# SynthEvaluationBoard.net
KiCad netlist of a schematic drawn in EAGLE
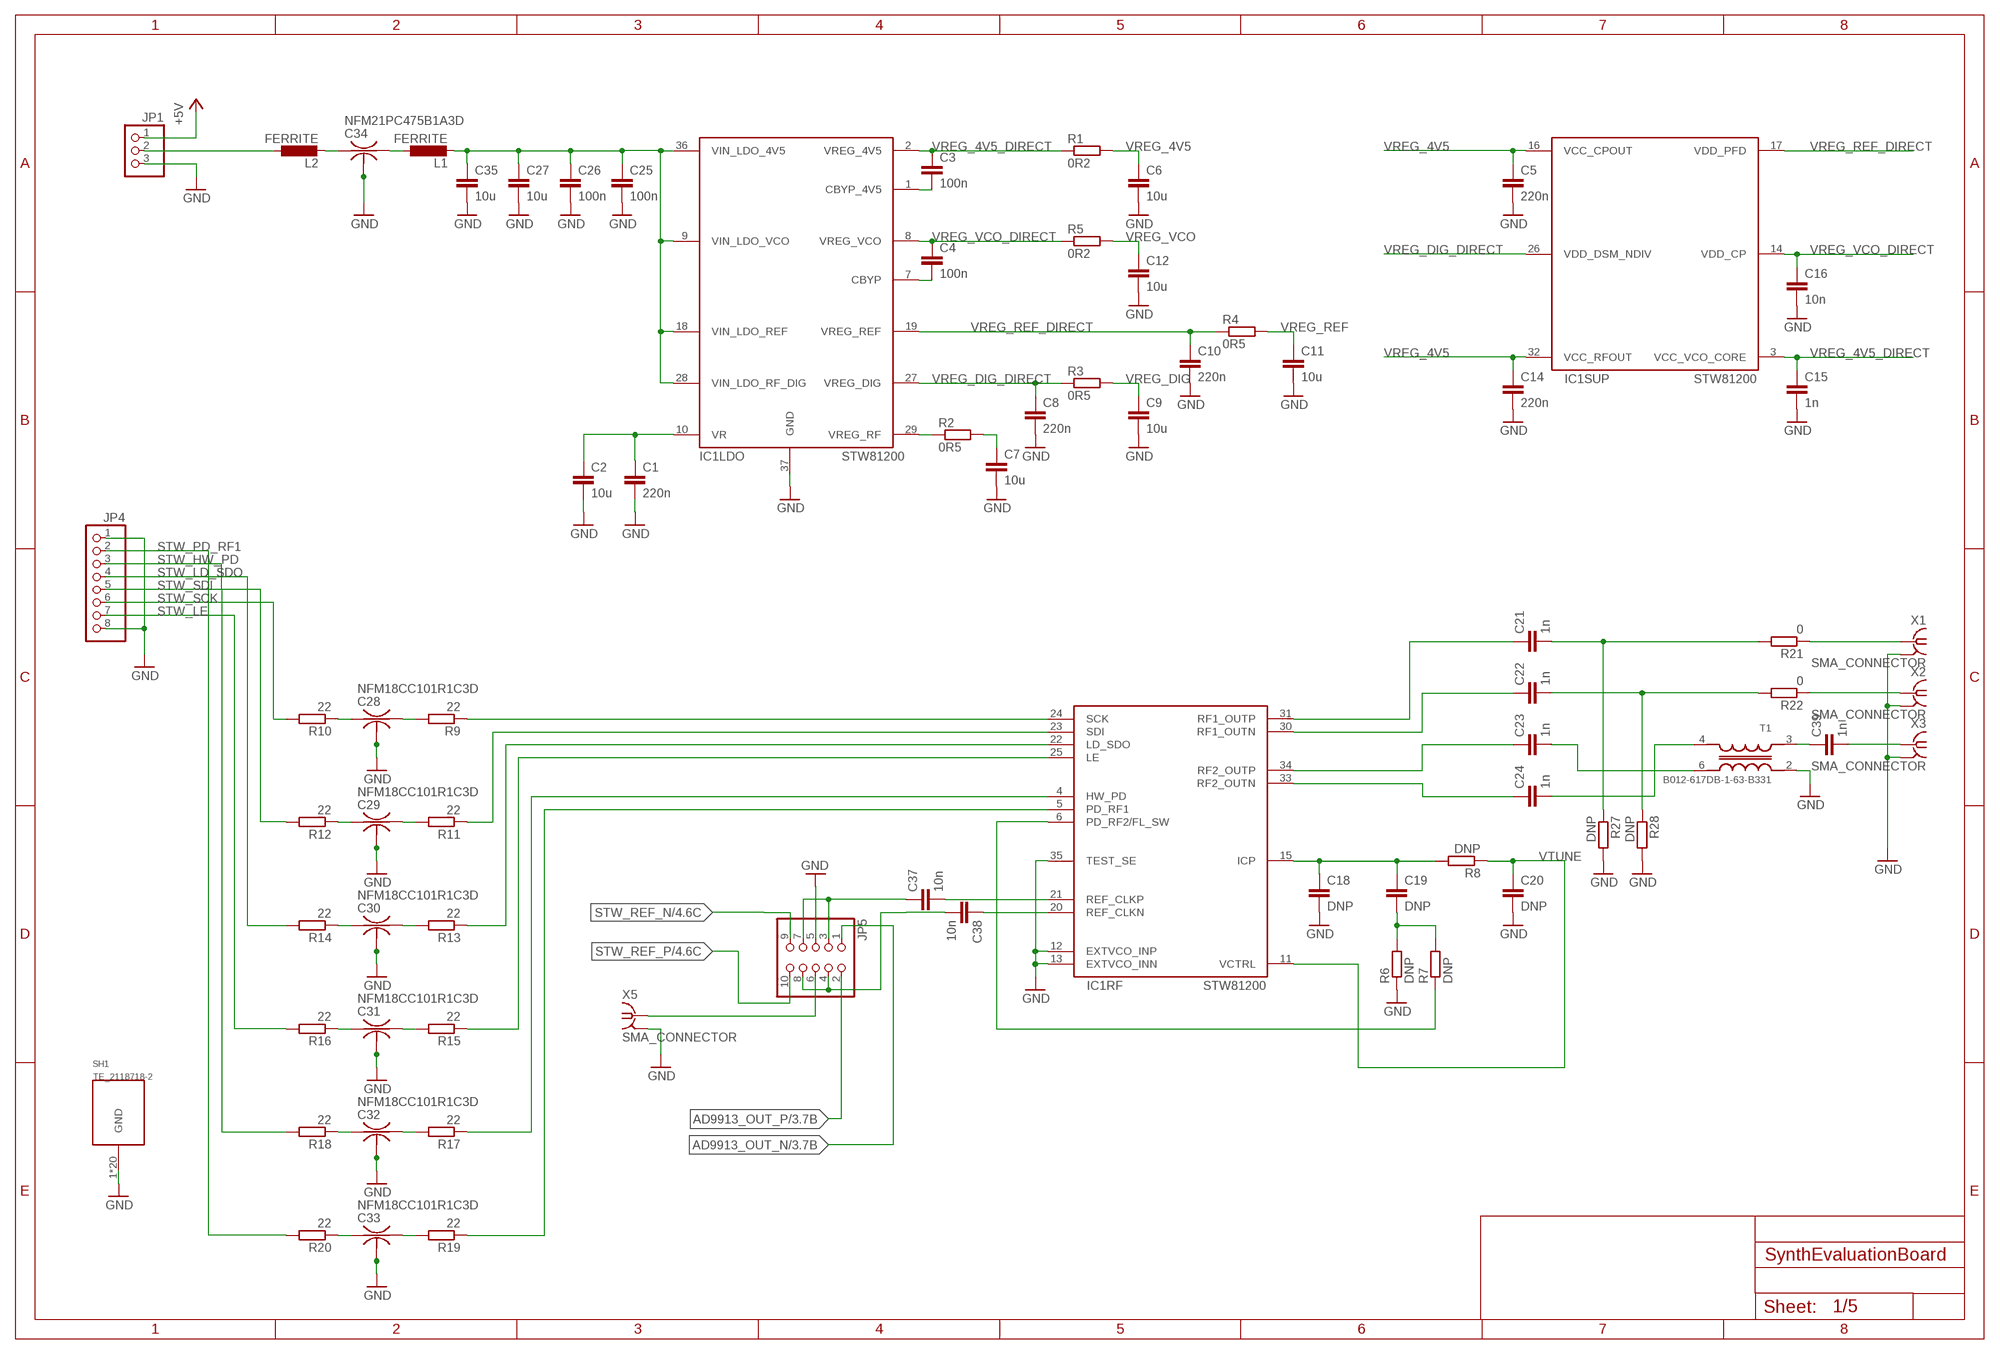
[diagram p0: schematic, sheet 1]
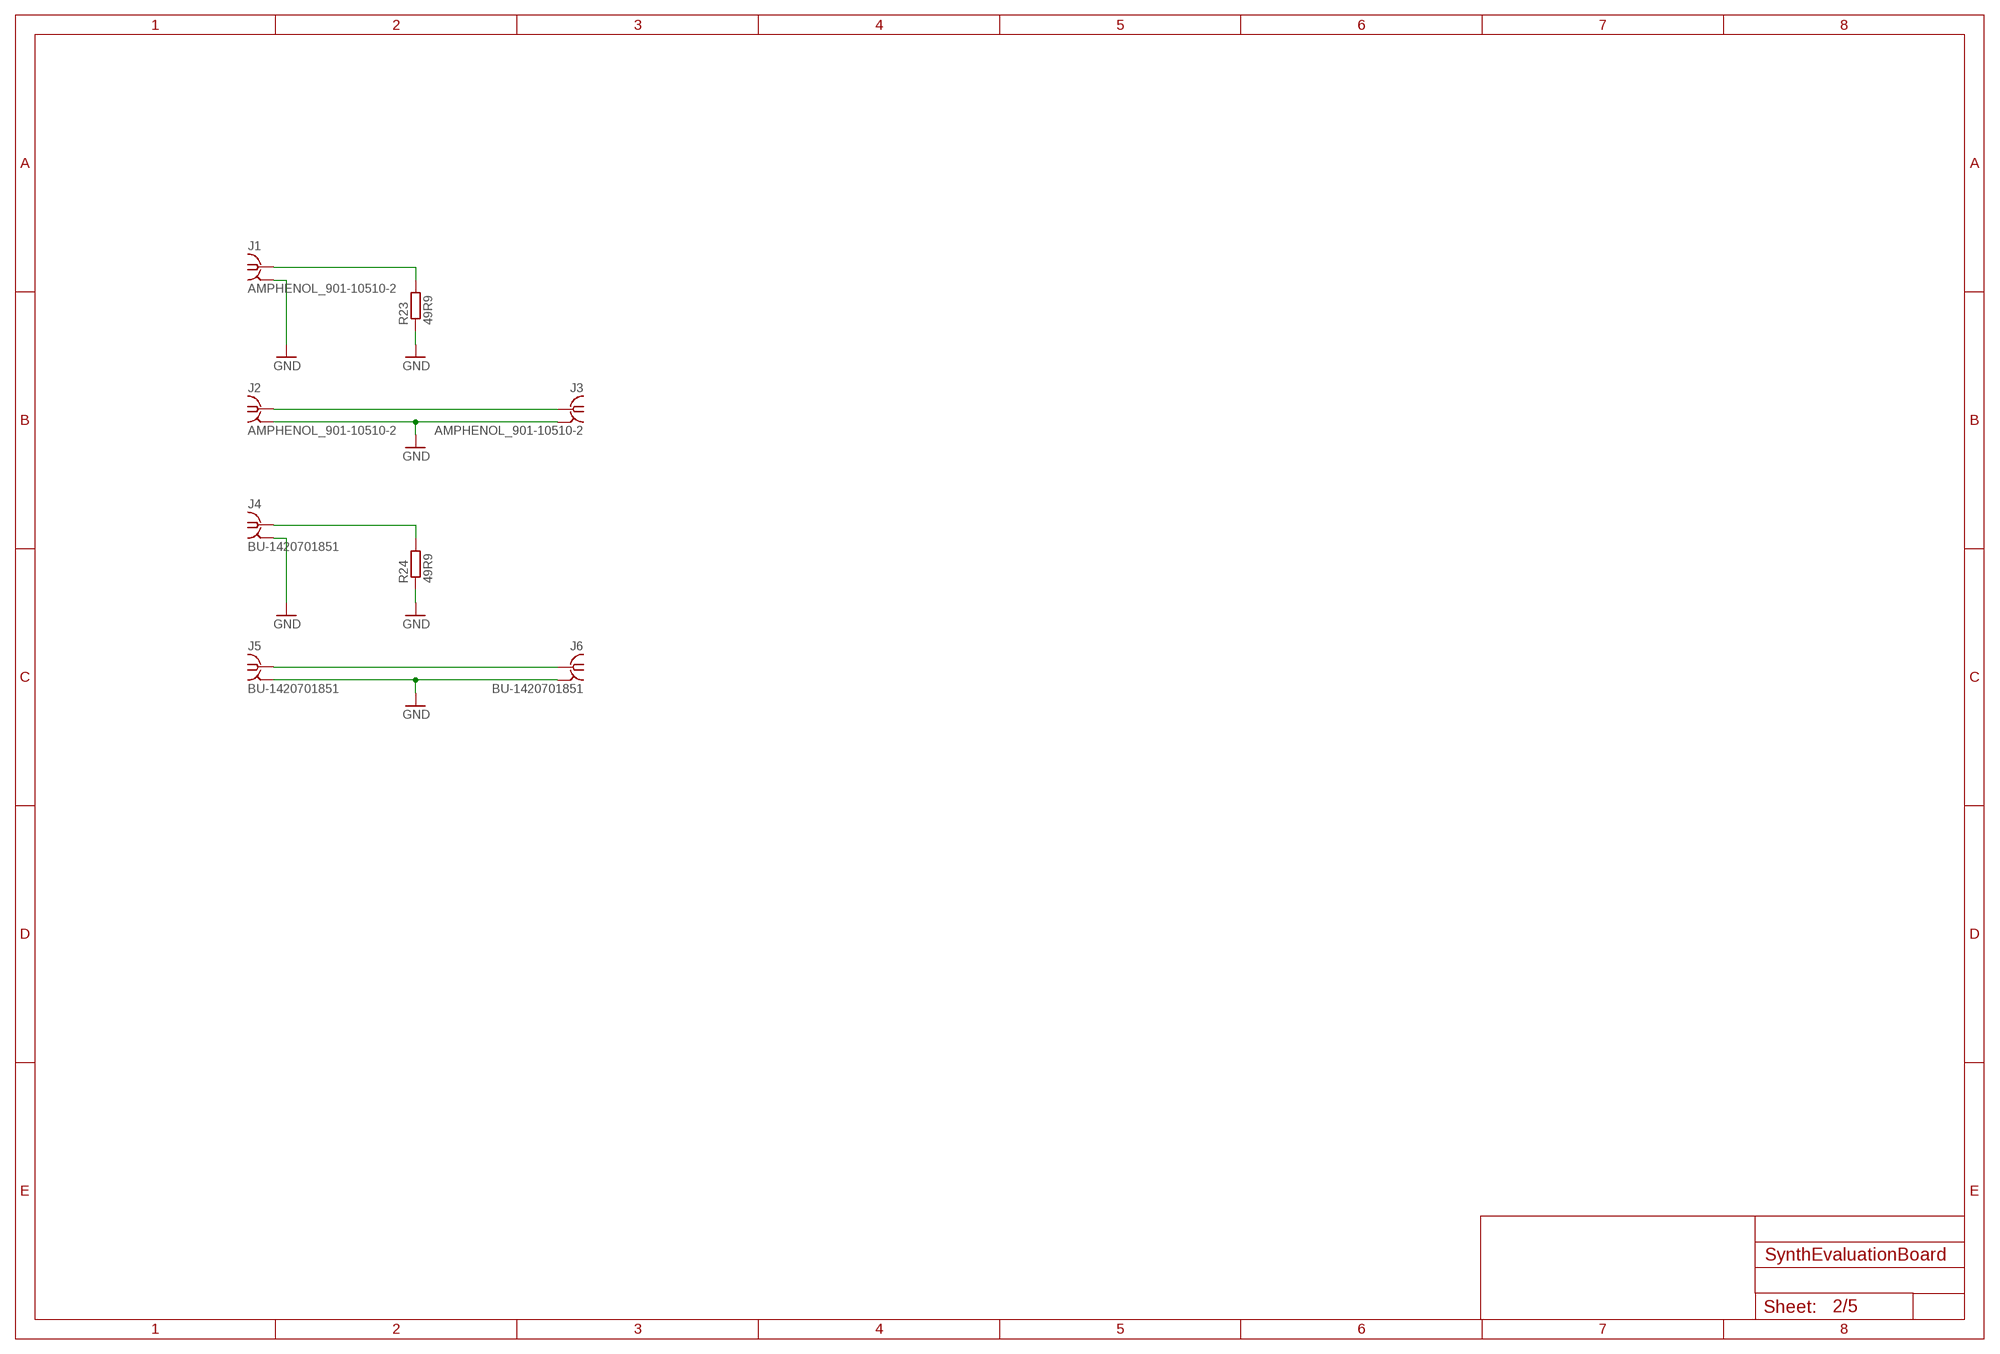
[diagram p1: schematic, sheet 2]
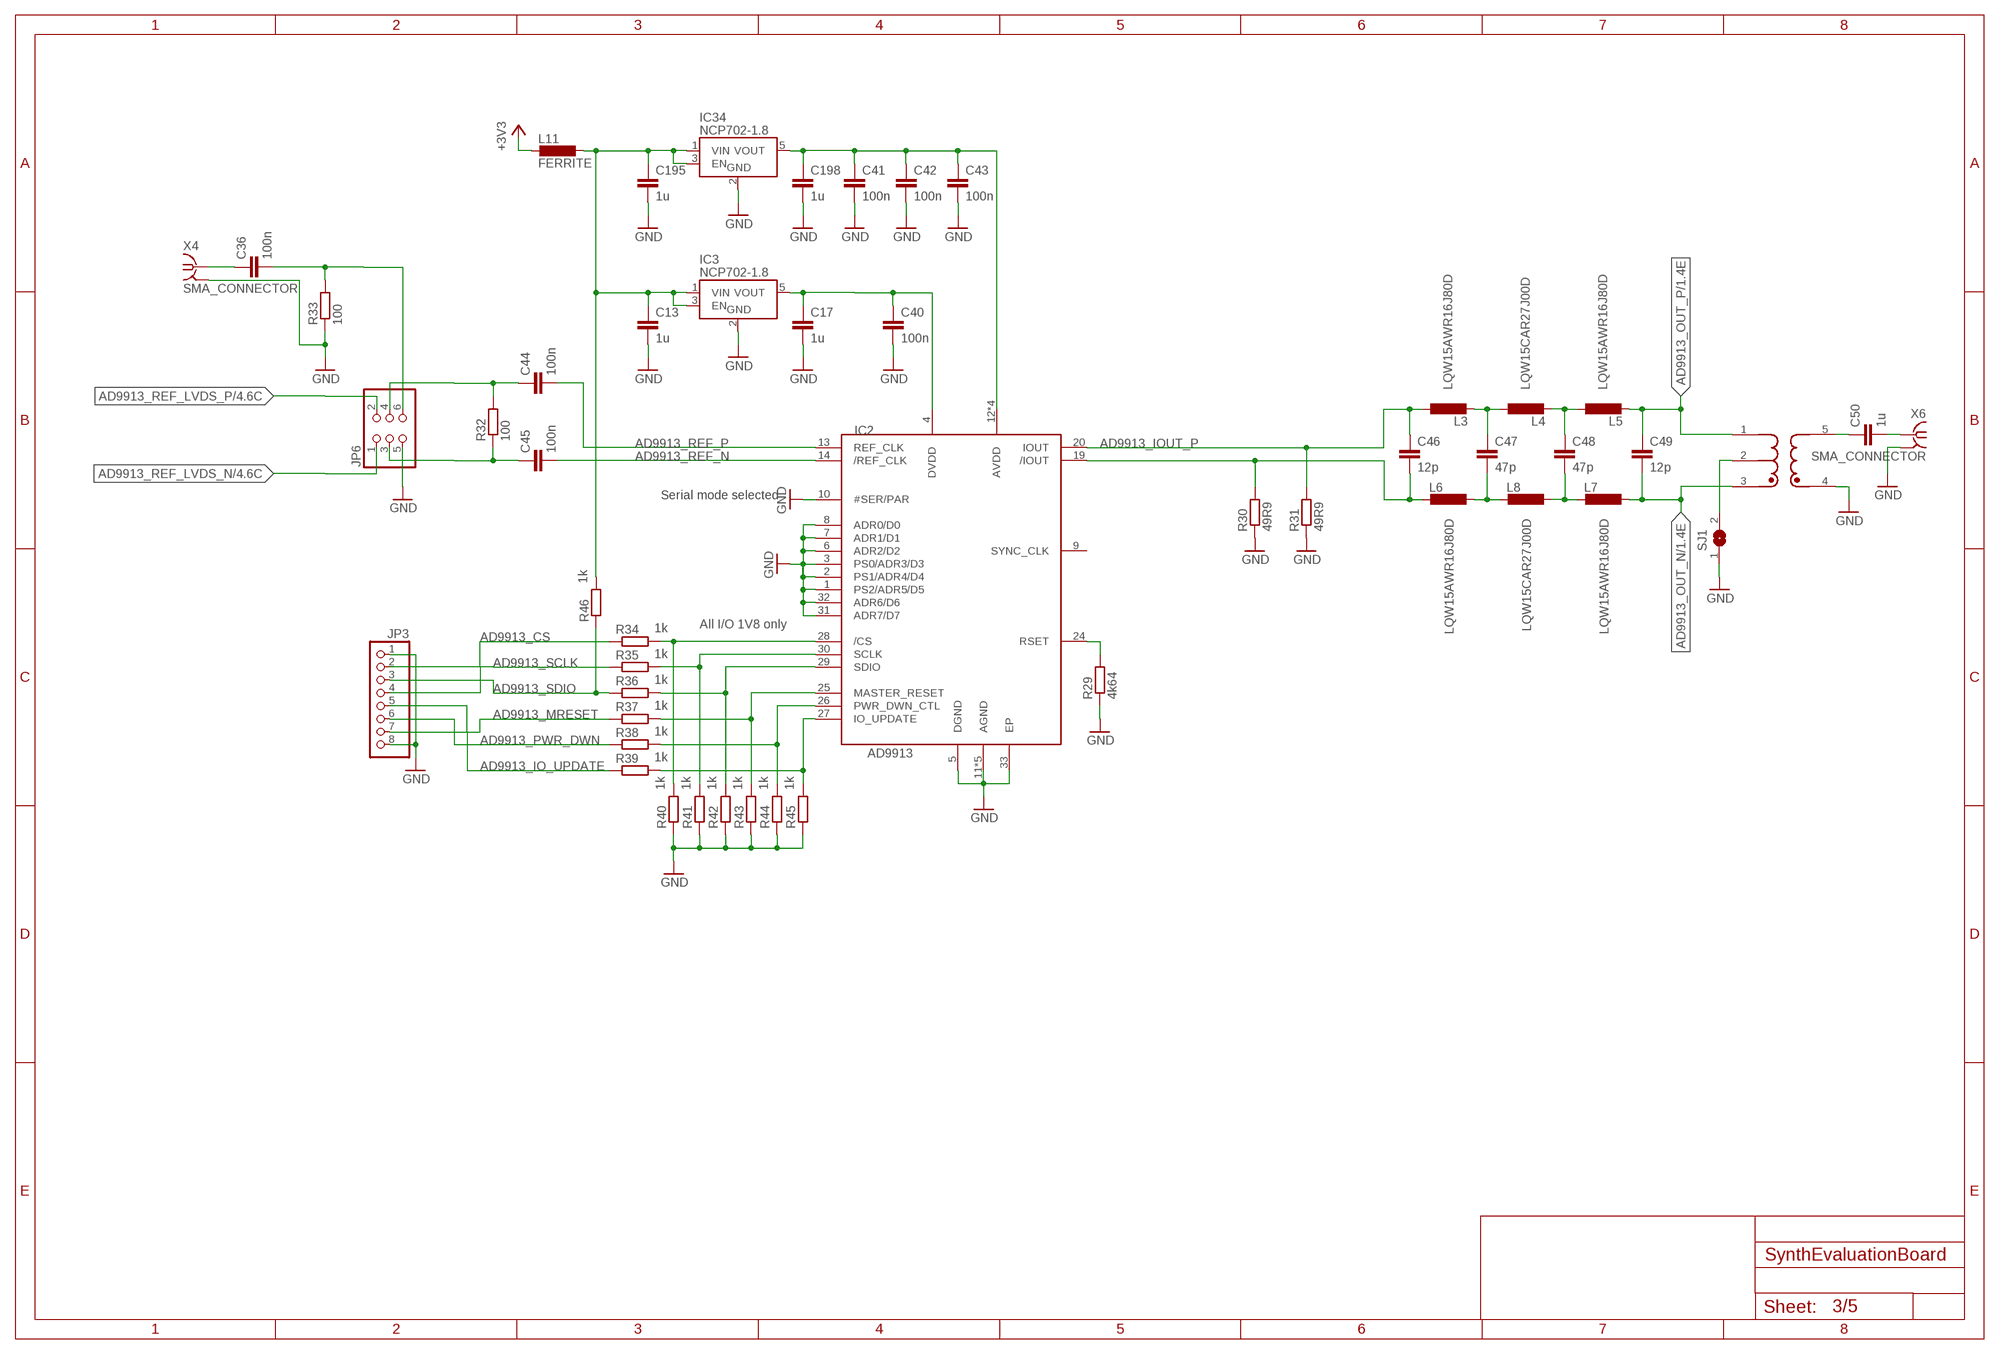
[diagram p2: schematic, sheet 3]
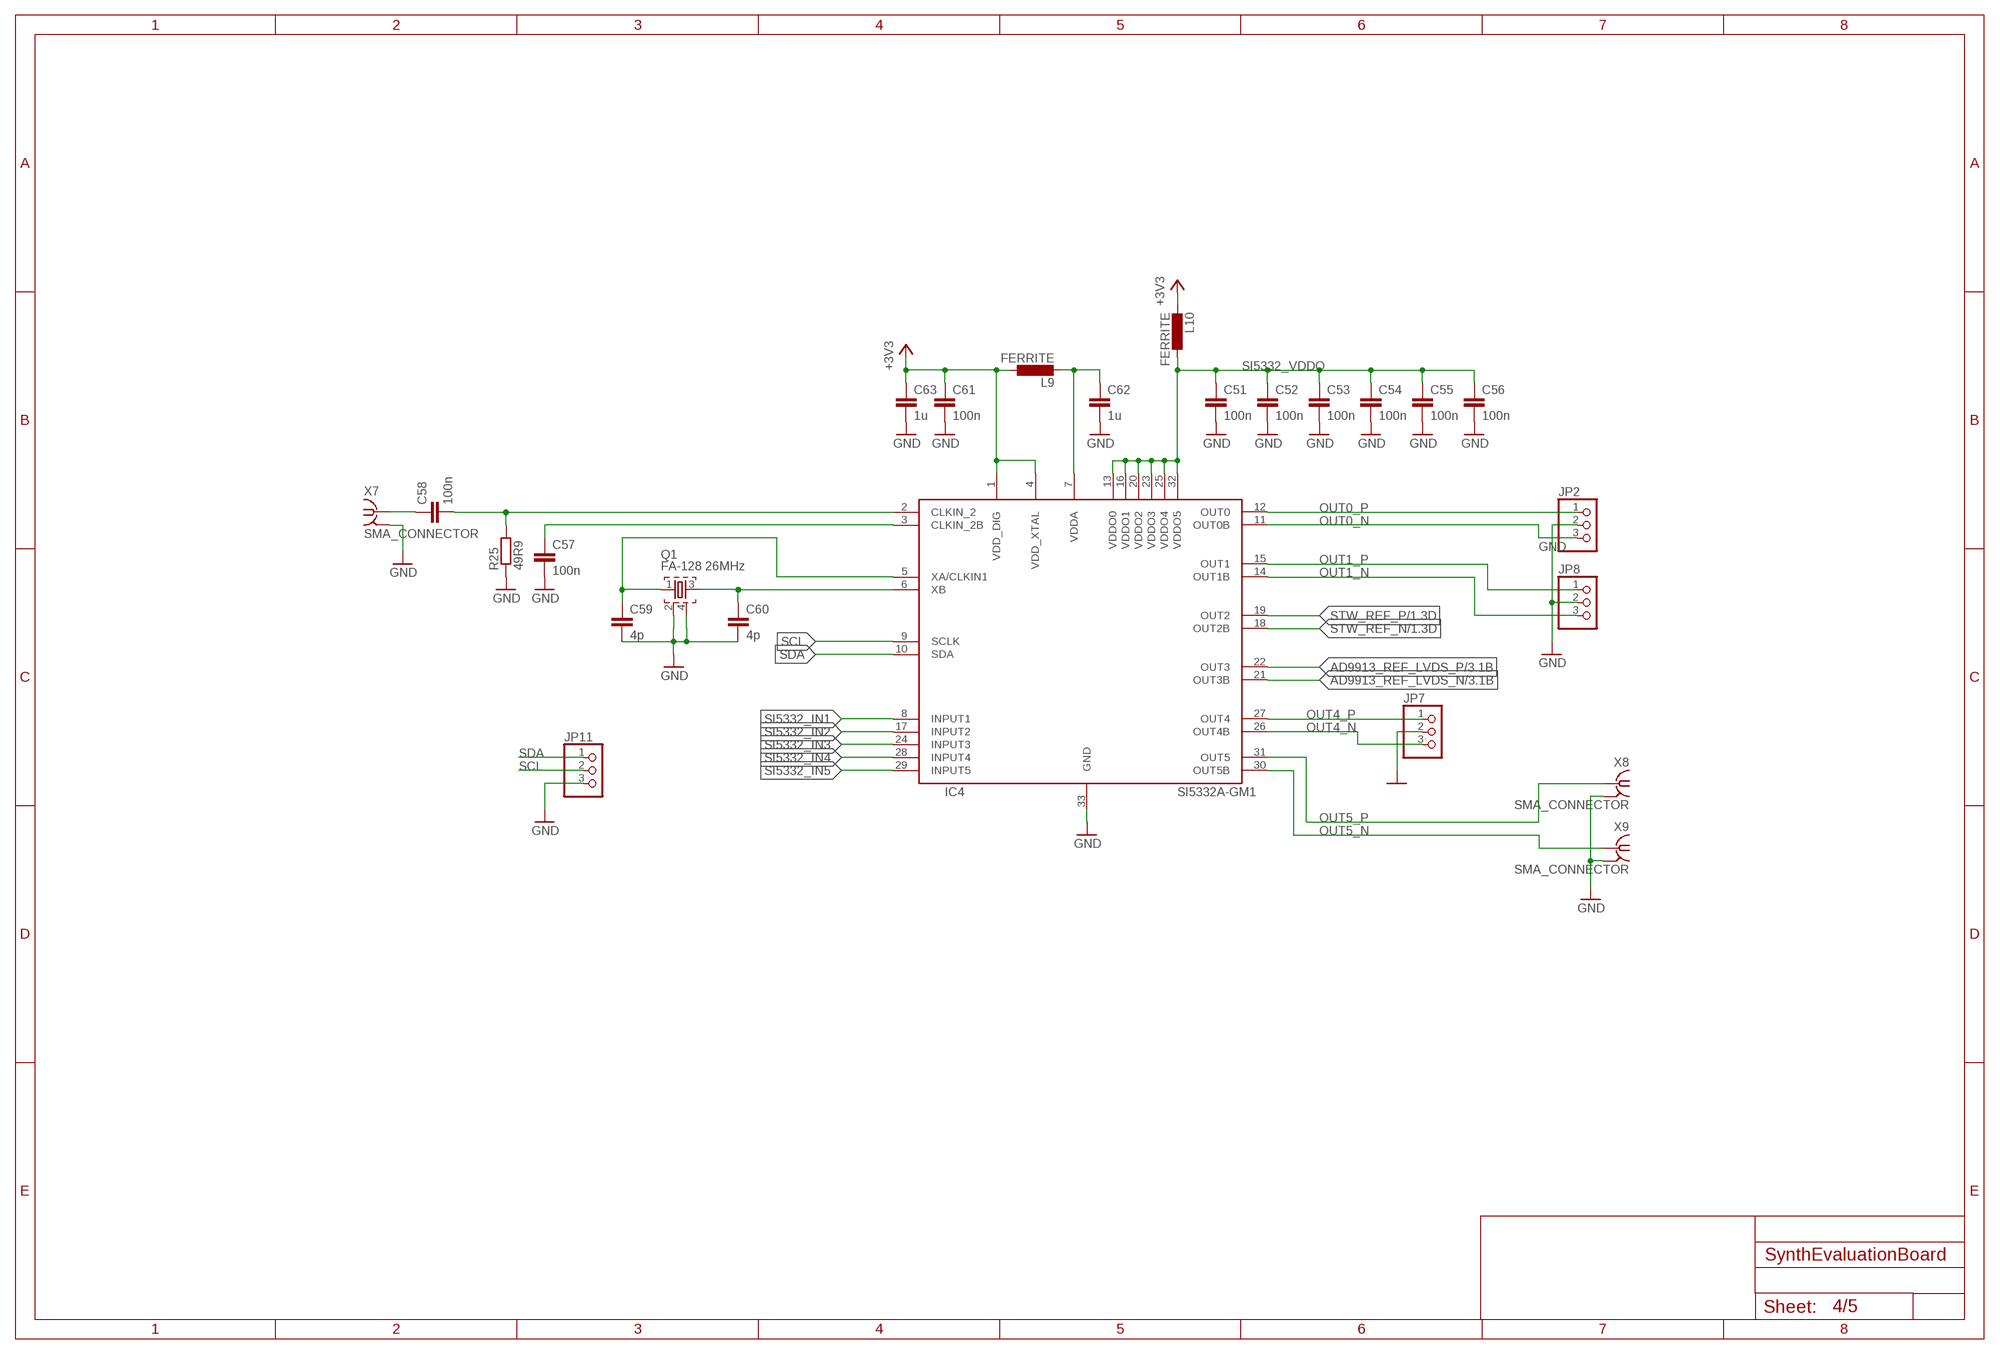
[diagram p3: schematic, sheet 4]
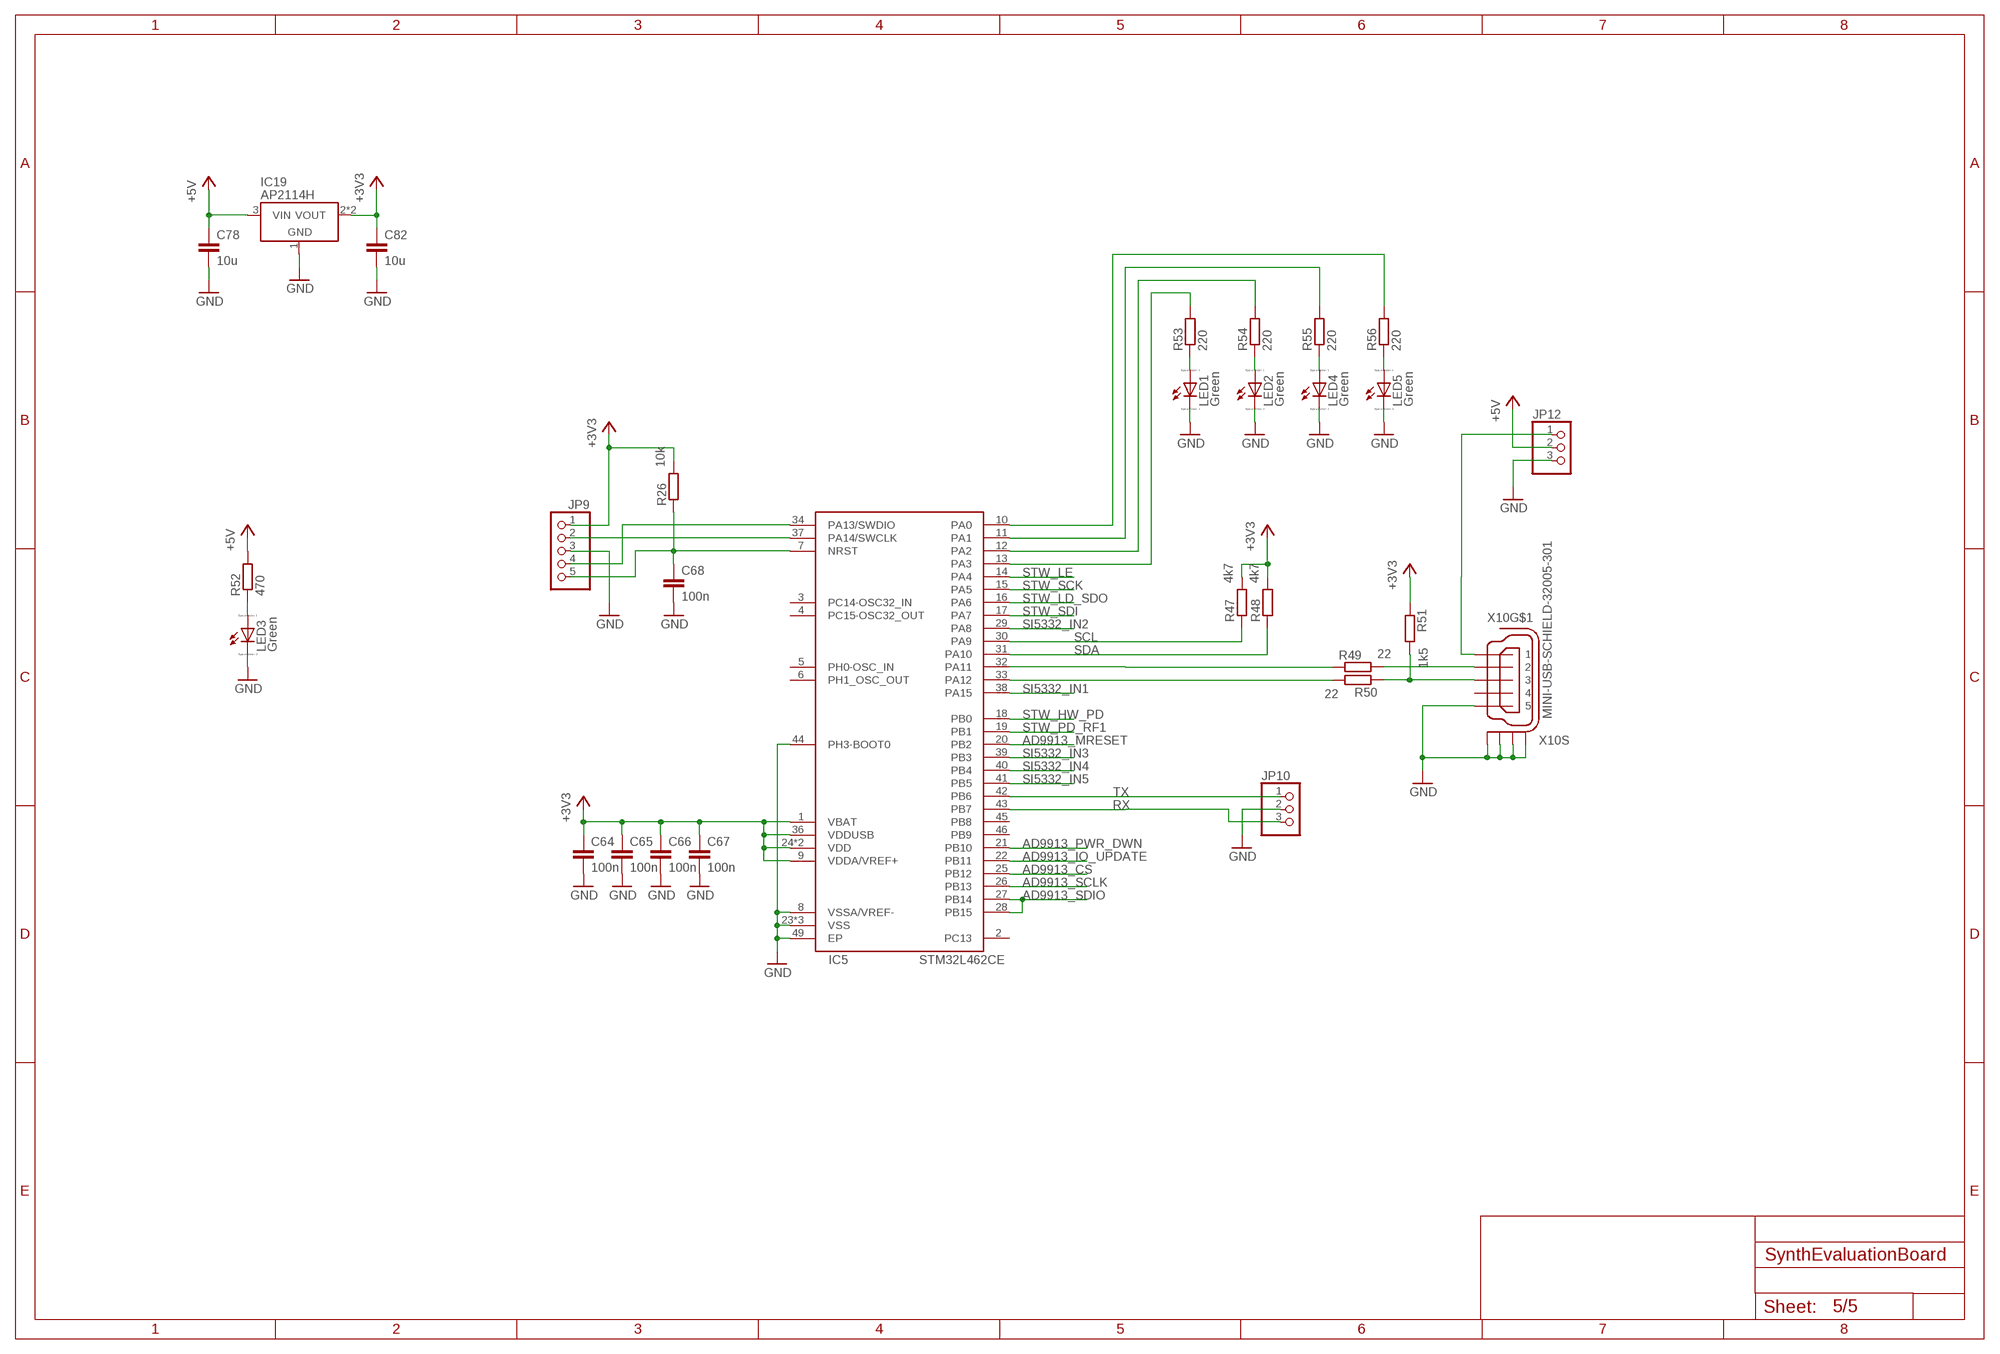
[diagram p4: schematic, sheet 5]

(export (version "E")
  (design (tool "Eeschema 10.0.6"))
  (components
    (comp (ref "C51")
      (value "100n")
      (footprint "eagle-import:C0402")
      (libsource (lib "eagle-import") (part "C-EU?{colon}2C0402"))
    )
    (comp (ref "C52")
      (value "100n")
      (footprint "eagle-import:C0402")
      (libsource (lib "eagle-import") (part "C-EU?{colon}2C0402"))
    )
    (comp (ref "C53")
      (value "100n")
      (footprint "eagle-import:C0402")
      (libsource (lib "eagle-import") (part "C-EU?{colon}2C0402"))
    )
    (comp (ref "C54")
      (value "100n")
      (footprint "eagle-import:C0402")
      (libsource (lib "eagle-import") (part "C-EU?{colon}2C0402"))
    )
    (comp (ref "C55")
      (value "100n")
      (footprint "eagle-import:C0402")
      (libsource (lib "eagle-import") (part "C-EU?{colon}2C0402"))
    )
    (comp (ref "C56")
      (value "100n")
      (footprint "eagle-import:C0402")
      (libsource (lib "eagle-import") (part "C-EU?{colon}2C0402"))
    )
    (comp (ref "C57")
      (value "100n")
      (footprint "eagle-import:C0402")
      (libsource (lib "eagle-import") (part "C-EU?{colon}2C0402"))
    )
    (comp (ref "C58")
      (value "100n")
      (footprint "eagle-import:C0402")
      (libsource (lib "eagle-import") (part "C-EU?{colon}2C0402"))
    )
    (comp (ref "C59")
      (value "4p")
      (footprint "eagle-import:C0402")
      (libsource (lib "eagle-import") (part "C-EU?{colon}2C0402"))
    )
    (comp (ref "C60")
      (value "4p")
      (footprint "eagle-import:C0402")
      (libsource (lib "eagle-import") (part "C-EU?{colon}2C0402"))
    )
    (comp (ref "C61")
      (value "100n")
      (footprint "eagle-import:C0402")
      (libsource (lib "eagle-import") (part "C-EU?{colon}2C0402"))
    )
    (comp (ref "C62")
      (value "1u")
      (footprint "eagle-import:C0402")
      (libsource (lib "eagle-import") (part "C-EU?{colon}2C0402"))
    )
    (comp (ref "C63")
      (value "1u")
      (footprint "eagle-import:C0402")
      (libsource (lib "eagle-import") (part "C-EU?{colon}2C0402"))
    )
    (comp (ref "IC4")
      (value "SI5332A-GM1")
      (footprint "eagle-import:QFN50P500X500X100-33T345N")
      (libsource (lib "eagle-import") (part "SI5332A-GM1"))
    )
    (comp (ref "JP2")
      (value "PINHD-1X3")
      (footprint "eagle-import:1X03")
      (libsource (lib "eagle-import") (part "PINHD-1X3"))
    )
    (comp (ref "JP7")
      (value "PINHD-1X3")
      (footprint "eagle-import:1X03")
      (libsource (lib "eagle-import") (part "PINHD-1X3"))
    )
    (comp (ref "JP8")
      (value "PINHD-1X3")
      (footprint "eagle-import:1X03")
      (libsource (lib "eagle-import") (part "PINHD-1X3"))
    )
    (comp (ref "JP11")
      (value "PINHD-1X3")
      (footprint "eagle-import:1X03")
      (libsource (lib "eagle-import") (part "PINHD-1X3"))
    )
    (comp (ref "L9")
      (value "FERRITE")
      (footprint "eagle-import:R0402")
      (libsource (lib "eagle-import") (part "FERRITE"))
    )
    (comp (ref "L10")
      (value "FERRITE")
      (footprint "eagle-import:R0402")
      (libsource (lib "eagle-import") (part "FERRITE"))
    )
    (comp (ref "Q1")
      (value "FA-128 26MHz")
      (footprint "eagle-import:FA-128")
      (libsource (lib "eagle-import") (part "FA-128"))
    )
    (comp (ref "R25")
      (value "49R9")
      (footprint "eagle-import:R0402")
      (libsource (lib "eagle-import") (part "R-EU_R0402"))
    )
    (comp (ref "X7")
      (value "SMA_CONNECTOR")
      (footprint "eagle-import:J502-ND-142-0711-821_826")
      (libsource (lib "eagle-import") (part "SMA_CONNECTOR"))
    )
    (comp (ref "X8")
      (value "SMA_CONNECTOR")
      (footprint "eagle-import:J502-ND-142-0711-821_826")
      (libsource (lib "eagle-import") (part "SMA_CONNECTOR"))
    )
    (comp (ref "X9")
      (value "SMA_CONNECTOR")
      (footprint "eagle-import:J502-ND-142-0711-821_826")
      (libsource (lib "eagle-import") (part "SMA_CONNECTOR"))
    )
    (comp (ref "B1")
      (value "ETC1-1T-2")
      (footprint "eagle-import:SM-22")
      (libsource (lib "eagle-import") (part "ETC1-1T"))
    )
    (comp (ref "C13")
      (value "1u")
      (footprint "eagle-import:C0402")
      (libsource (lib "eagle-import") (part "C-EU?{colon}2C0402"))
    )
    (comp (ref "C17")
      (value "1u")
      (footprint "eagle-import:C0402")
      (libsource (lib "eagle-import") (part "C-EU?{colon}2C0402"))
    )
    (comp (ref "C36")
      (value "100n")
      (footprint "eagle-import:C0402")
      (libsource (lib "eagle-import") (part "C-EU?{colon}2C0402"))
    )
    (comp (ref "C40")
      (value "100n")
      (footprint "eagle-import:C0402")
      (libsource (lib "eagle-import") (part "C-EU?{colon}2C0402"))
    )
    (comp (ref "C41")
      (value "100n")
      (footprint "eagle-import:C0402")
      (libsource (lib "eagle-import") (part "C-EU?{colon}2C0402"))
    )
    (comp (ref "C42")
      (value "100n")
      (footprint "eagle-import:C0402")
      (libsource (lib "eagle-import") (part "C-EU?{colon}2C0402"))
    )
    (comp (ref "C43")
      (value "100n")
      (footprint "eagle-import:C0402")
      (libsource (lib "eagle-import") (part "C-EU?{colon}2C0402"))
    )
    (comp (ref "C44")
      (value "100n")
      (footprint "eagle-import:C0402")
      (libsource (lib "eagle-import") (part "C-EU?{colon}2C0402"))
    )
    (comp (ref "C45")
      (value "100n")
      (footprint "eagle-import:C0402")
      (libsource (lib "eagle-import") (part "C-EU?{colon}2C0402"))
    )
    (comp (ref "C46")
      (value "12p")
      (footprint "eagle-import:C0402")
      (libsource (lib "eagle-import") (part "C-EU?{colon}2C0402"))
    )
    (comp (ref "C47")
      (value "47p")
      (footprint "eagle-import:C0402")
      (libsource (lib "eagle-import") (part "C-EU?{colon}2C0402"))
    )
    (comp (ref "C48")
      (value "47p")
      (footprint "eagle-import:C0402")
      (libsource (lib "eagle-import") (part "C-EU?{colon}2C0402"))
    )
    (comp (ref "C49")
      (value "12p")
      (footprint "eagle-import:C0402")
      (libsource (lib "eagle-import") (part "C-EU?{colon}2C0402"))
    )
    (comp (ref "C50")
      (value "1u")
      (footprint "eagle-import:C0402")
      (libsource (lib "eagle-import") (part "C-EU?{colon}2C0402"))
    )
    (comp (ref "C195")
      (value "1u")
      (footprint "eagle-import:C0402")
      (libsource (lib "eagle-import") (part "C-EU?{colon}2C0402"))
    )
    (comp (ref "C198")
      (value "1u")
      (footprint "eagle-import:C0402")
      (libsource (lib "eagle-import") (part "C-EU?{colon}2C0402"))
    )
    (comp (ref "IC2")
      (value "AD9913")
      (footprint "eagle-import:QFN50P500X500X80-33T310")
      (libsource (lib "eagle-import") (part "AD9913"))
    )
    (comp (ref "IC3")
      (value "NCP702-1.8")
      (footprint "eagle-import:SOT95P240X110-5")
      (libsource (lib "eagle-import") (part "NCP702"))
    )
    (comp (ref "IC34")
      (value "NCP702-1.8")
      (footprint "eagle-import:SOT95P240X110-5")
      (libsource (lib "eagle-import") (part "NCP702"))
    )
    (comp (ref "JP3")
      (value "PINHD-1X8")
      (footprint "eagle-import:1X08")
      (libsource (lib "eagle-import") (part "PINHD-1X8"))
    )
    (comp (ref "JP6")
      (value "PINHD-2X3")
      (footprint "eagle-import:2X03")
      (libsource (lib "eagle-import") (part "PINHD-2X3"))
    )
    (comp (ref "L3")
      (value "LQW15AWR16J80D")
      (footprint "eagle-import:L0402")
      (libsource (lib "eagle-import") (part "INDUCTOR0402"))
    )
    (comp (ref "L4")
      (value "LQW15CAR27J00D")
      (footprint "eagle-import:L0402")
      (libsource (lib "eagle-import") (part "INDUCTOR0402"))
    )
    (comp (ref "L5")
      (value "LQW15AWR16J80D")
      (footprint "eagle-import:L0402")
      (libsource (lib "eagle-import") (part "INDUCTOR0402"))
    )
    (comp (ref "L6")
      (value "LQW15AWR16J80D")
      (footprint "eagle-import:L0402")
      (libsource (lib "eagle-import") (part "INDUCTOR0402"))
    )
    (comp (ref "L7")
      (value "LQW15AWR16J80D")
      (footprint "eagle-import:L0402")
      (libsource (lib "eagle-import") (part "INDUCTOR0402"))
    )
    (comp (ref "L8")
      (value "LQW15CAR27J00D")
      (footprint "eagle-import:L0402")
      (libsource (lib "eagle-import") (part "INDUCTOR0402"))
    )
    (comp (ref "L11")
      (value "FERRITE")
      (footprint "eagle-import:R0402")
      (libsource (lib "eagle-import") (part "FERRITE"))
    )
    (comp (ref "R29")
      (value "4k64")
      (footprint "eagle-import:R0402")
      (libsource (lib "eagle-import") (part "R-EU_R0402"))
    )
    (comp (ref "R30")
      (value "49R9")
      (footprint "eagle-import:R0402")
      (libsource (lib "eagle-import") (part "R-EU_R0402"))
    )
    (comp (ref "R31")
      (value "49R9")
      (footprint "eagle-import:R0402")
      (libsource (lib "eagle-import") (part "R-EU_R0402"))
    )
    (comp (ref "R32")
      (value "100")
      (footprint "eagle-import:R0402")
      (libsource (lib "eagle-import") (part "R-EU_R0402"))
    )
    (comp (ref "R33")
      (value "100")
      (footprint "eagle-import:R0402")
      (libsource (lib "eagle-import") (part "R-EU_R0402"))
    )
    (comp (ref "R34")
      (value "1k")
      (footprint "eagle-import:R0402")
      (libsource (lib "eagle-import") (part "R-EU_R0402"))
    )
    (comp (ref "R35")
      (value "1k")
      (footprint "eagle-import:R0402")
      (libsource (lib "eagle-import") (part "R-EU_R0402"))
    )
    (comp (ref "R36")
      (value "1k")
      (footprint "eagle-import:R0402")
      (libsource (lib "eagle-import") (part "R-EU_R0402"))
    )
    (comp (ref "R37")
      (value "1k")
      (footprint "eagle-import:R0402")
      (libsource (lib "eagle-import") (part "R-EU_R0402"))
    )
    (comp (ref "R38")
      (value "1k")
      (footprint "eagle-import:R0402")
      (libsource (lib "eagle-import") (part "R-EU_R0402"))
    )
    (comp (ref "R39")
      (value "1k")
      (footprint "eagle-import:R0402")
      (libsource (lib "eagle-import") (part "R-EU_R0402"))
    )
    (comp (ref "R40")
      (value "1k")
      (footprint "eagle-import:R0402")
      (libsource (lib "eagle-import") (part "R-EU_R0402"))
    )
    (comp (ref "R41")
      (value "1k")
      (footprint "eagle-import:R0402")
      (libsource (lib "eagle-import") (part "R-EU_R0402"))
    )
    (comp (ref "R42")
      (value "1k")
      (footprint "eagle-import:R0402")
      (libsource (lib "eagle-import") (part "R-EU_R0402"))
    )
    (comp (ref "R43")
      (value "1k")
      (footprint "eagle-import:R0402")
      (libsource (lib "eagle-import") (part "R-EU_R0402"))
    )
    (comp (ref "R44")
      (value "1k")
      (footprint "eagle-import:R0402")
      (libsource (lib "eagle-import") (part "R-EU_R0402"))
    )
    (comp (ref "R45")
      (value "1k")
      (footprint "eagle-import:R0402")
      (libsource (lib "eagle-import") (part "R-EU_R0402"))
    )
    (comp (ref "R46")
      (value "1k")
      (footprint "eagle-import:R0402")
      (libsource (lib "eagle-import") (part "R-EU_R0402"))
    )
    (comp (ref "SJ1") (value "SJ") (footprint "eagle-import:SJ") (libsource (lib "eagle-import") (part "SJ")))
    (comp (ref "X4")
      (value "SMA_CONNECTOR")
      (footprint "eagle-import:J502-ND-142-0711-821_826")
      (libsource (lib "eagle-import") (part "SMA_CONNECTOR"))
    )
    (comp (ref "X6")
      (value "SMA_CONNECTOR")
      (footprint "eagle-import:J502-ND-142-0711-821_826")
      (libsource (lib "eagle-import") (part "SMA_CONNECTOR"))
    )
    (comp (ref "J1")
      (value "AMPHENOL_901-10510-2")
      (footprint "eagle-import:AMPHENOL_901-10510-2")
      (libsource (lib "eagle-import") (part "AMPHENOL_901-10510-2"))
    )
    (comp (ref "J2")
      (value "AMPHENOL_901-10510-2")
      (footprint "eagle-import:AMPHENOL_901-10510-2")
      (libsource (lib "eagle-import") (part "AMPHENOL_901-10510-2"))
    )
    (comp (ref "J3")
      (value "AMPHENOL_901-10510-2")
      (footprint "eagle-import:AMPHENOL_901-10510-2")
      (libsource (lib "eagle-import") (part "AMPHENOL_901-10510-2"))
    )
    (comp (ref "J4")
      (value "BU-1420701851")
      (footprint "eagle-import:BU-1420701851")
      (libsource (lib "eagle-import") (part "BU-1420701851"))
    )
    (comp (ref "J5")
      (value "BU-1420701851")
      (footprint "eagle-import:BU-1420701851")
      (libsource (lib "eagle-import") (part "BU-1420701851"))
    )
    (comp (ref "J6")
      (value "BU-1420701851")
      (footprint "eagle-import:BU-1420701851")
      (libsource (lib "eagle-import") (part "BU-1420701851"))
    )
    (comp (ref "R23")
      (value "49R9")
      (footprint "eagle-import:R0402")
      (libsource (lib "eagle-import") (part "R-EU_R0402"))
    )
    (comp (ref "R24")
      (value "49R9")
      (footprint "eagle-import:R0402")
      (libsource (lib "eagle-import") (part "R-EU_R0402"))
    )
    (comp (ref "C64")
      (value "100n")
      (footprint "eagle-import:C0402")
      (libsource (lib "eagle-import") (part "C-EU?{colon}2C0402"))
    )
    (comp (ref "C65")
      (value "100n")
      (footprint "eagle-import:C0402")
      (libsource (lib "eagle-import") (part "C-EU?{colon}2C0402"))
    )
    (comp (ref "C66")
      (value "100n")
      (footprint "eagle-import:C0402")
      (libsource (lib "eagle-import") (part "C-EU?{colon}2C0402"))
    )
    (comp (ref "C67")
      (value "100n")
      (footprint "eagle-import:C0402")
      (libsource (lib "eagle-import") (part "C-EU?{colon}2C0402"))
    )
    (comp (ref "C68")
      (value "100n")
      (footprint "eagle-import:C0402")
      (libsource (lib "eagle-import") (part "C-EU?{colon}2C0402"))
    )
    (comp (ref "C78")
      (value "10u")
      (footprint "eagle-import:C1206")
      (libsource (lib "eagle-import") (part "C-EUC1206"))
    )
    (comp (ref "C82")
      (value "10u")
      (footprint "eagle-import:C1206")
      (libsource (lib "eagle-import") (part "C-EUC1206"))
    )
    (comp (ref "IC5")
      (value "STM32L462CE")
      (footprint "eagle-import:QFN50P700X700X60-49T560N")
      (libsource (lib "eagle-import") (part "STM32L462CE"))
    )
    (comp (ref "IC19")
      (value "AP2114H")
      (footprint "eagle-import:SOT230P700X180-4")
      (libsource (lib "eagle-import") (part "AP2114H"))
    )
    (comp (ref "JP9")
      (value "PINHD-1X5")
      (footprint "eagle-import:1X05")
      (libsource (lib "eagle-import") (part "PINHD-1X5"))
    )
    (comp (ref "JP10")
      (value "PINHD-1X3")
      (footprint "eagle-import:1X03")
      (libsource (lib "eagle-import") (part "PINHD-1X3"))
    )
    (comp (ref "JP12")
      (value "PINHD-1X3")
      (footprint "eagle-import:1X03")
      (libsource (lib "eagle-import") (part "PINHD-1X3"))
    )
    (comp (ref "LED1")
      (value "Green")
      (footprint "eagle-import:LED_SML0603")
      (libsource (lib "eagle-import") (part "LED_ESML0603"))
    )
    (comp (ref "LED2")
      (value "Green")
      (footprint "eagle-import:LED_SML0603")
      (libsource (lib "eagle-import") (part "LED_ESML0603"))
    )
    (comp (ref "LED3")
      (value "Green")
      (footprint "eagle-import:LED_SML0603")
      (libsource (lib "eagle-import") (part "LED_ESML0603"))
    )
    (comp (ref "LED4")
      (value "Green")
      (footprint "eagle-import:LED_SML0603")
      (libsource (lib "eagle-import") (part "LED_ESML0603"))
    )
    (comp (ref "LED5")
      (value "Green")
      (footprint "eagle-import:LED_SML0603")
      (libsource (lib "eagle-import") (part "LED_ESML0603"))
    )
    (comp (ref "R26")
      (value "10k")
      (footprint "eagle-import:R0402")
      (libsource (lib "eagle-import") (part "R-EU_R0402"))
    )
    (comp (ref "R47")
      (value "4k7")
      (footprint "eagle-import:R0402")
      (libsource (lib "eagle-import") (part "R-EU_R0402"))
    )
    (comp (ref "R48")
      (value "4k7")
      (footprint "eagle-import:R0402")
      (libsource (lib "eagle-import") (part "R-EU_R0402"))
    )
    (comp (ref "R49")
      (value "22")
      (footprint "eagle-import:R0402")
      (libsource (lib "eagle-import") (part "R-EU_R0402"))
    )
    (comp (ref "R50")
      (value "22")
      (footprint "eagle-import:R0402")
      (libsource (lib "eagle-import") (part "R-EU_R0402"))
    )
    (comp (ref "R51")
      (value "1k5")
      (footprint "eagle-import:R0402")
      (libsource (lib "eagle-import") (part "R-EU_R0402"))
    )
    (comp (ref "R52")
      (value "470")
      (footprint "eagle-import:R0402")
      (libsource (lib "eagle-import") (part "R-EU_R0402"))
    )
    (comp (ref "R53")
      (value "220")
      (footprint "eagle-import:R0402")
      (libsource (lib "eagle-import") (part "R-EU_R0402"))
    )
    (comp (ref "R54")
      (value "220")
      (footprint "eagle-import:R0402")
      (libsource (lib "eagle-import") (part "R-EU_R0402"))
    )
    (comp (ref "R55")
      (value "220")
      (footprint "eagle-import:R0402")
      (libsource (lib "eagle-import") (part "R-EU_R0402"))
    )
    (comp (ref "R56")
      (value "220")
      (footprint "eagle-import:R0402")
      (libsource (lib "eagle-import") (part "R-EU_R0402"))
    )
    (comp (ref "X10")
      (value "MINI-USB-SCHIELD-32005-301")
      (footprint "eagle-import:32005-301")
      (libsource (lib "eagle-import") (part "MINI-USB-SCHIELD-32005-301"))
    )
    (comp (ref "C1")
      (value "220n")
      (footprint "eagle-import:C0402")
      (libsource (lib "eagle-import") (part "C-EUC0402"))
    )
    (comp (ref "C2")
      (value "10u")
      (footprint "eagle-import:C0603")
      (libsource (lib "eagle-import") (part "rcl_334_C-EUC0603"))
    )
    (comp (ref "C3")
      (value "100n")
      (footprint "eagle-import:C0402")
      (libsource (lib "eagle-import") (part "C-EUC0402"))
    )
    (comp (ref "C4")
      (value "100n")
      (footprint "eagle-import:C0402")
      (libsource (lib "eagle-import") (part "C-EUC0402"))
    )
    (comp (ref "C5")
      (value "220n")
      (footprint "eagle-import:C0402")
      (libsource (lib "eagle-import") (part "C-EUC0402"))
    )
    (comp (ref "C6")
      (value "10u")
      (footprint "eagle-import:C0603")
      (libsource (lib "eagle-import") (part "rcl_334_C-EUC0603"))
    )
    (comp (ref "C7")
      (value "10u")
      (footprint "eagle-import:C0603")
      (libsource (lib "eagle-import") (part "rcl_334_C-EUC0603"))
    )
    (comp (ref "C8")
      (value "220n")
      (footprint "eagle-import:C0402")
      (libsource (lib "eagle-import") (part "C-EUC0402"))
    )
    (comp (ref "C9")
      (value "10u")
      (footprint "eagle-import:C0603")
      (libsource (lib "eagle-import") (part "rcl_334_C-EUC0603"))
    )
    (comp (ref "C10")
      (value "220n")
      (footprint "eagle-import:C0402")
      (libsource (lib "eagle-import") (part "C-EUC0402"))
    )
    (comp (ref "C11")
      (value "10u")
      (footprint "eagle-import:C0603")
      (libsource (lib "eagle-import") (part "rcl_334_C-EUC0603"))
    )
    (comp (ref "C12")
      (value "10u")
      (footprint "eagle-import:C0603")
      (libsource (lib "eagle-import") (part "rcl_334_C-EUC0603"))
    )
    (comp (ref "C14")
      (value "220n")
      (footprint "eagle-import:C0402")
      (libsource (lib "eagle-import") (part "C-EUC0402"))
    )
    (comp (ref "C15")
      (value "1n")
      (footprint "eagle-import:C0402")
      (libsource (lib "eagle-import") (part "C-EUC0402"))
    )
    (comp (ref "C16")
      (value "10n")
      (footprint "eagle-import:C0402")
      (libsource (lib "eagle-import") (part "C-EUC0402"))
    )
    (comp (ref "C18")
      (value "DNP")
      (footprint "eagle-import:C0402")
      (libsource (lib "eagle-import") (part "C-EUC0402"))
    )
    (comp (ref "C19")
      (value "DNP")
      (footprint "eagle-import:C0402")
      (libsource (lib "eagle-import") (part "C-EUC0402"))
    )
    (comp (ref "C20")
      (value "DNP")
      (footprint "eagle-import:C0402")
      (libsource (lib "eagle-import") (part "C-EUC0402"))
    )
    (comp (ref "C21")
      (value "1n")
      (footprint "eagle-import:C0402")
      (libsource (lib "eagle-import") (part "C-EUC0402"))
    )
    (comp (ref "C22")
      (value "1n")
      (footprint "eagle-import:C0402")
      (libsource (lib "eagle-import") (part "C-EUC0402"))
    )
    (comp (ref "C23")
      (value "1n")
      (footprint "eagle-import:C0402")
      (libsource (lib "eagle-import") (part "C-EUC0402"))
    )
    (comp (ref "C24")
      (value "1n")
      (footprint "eagle-import:C0402")
      (libsource (lib "eagle-import") (part "C-EUC0402"))
    )
    (comp (ref "C25")
      (value "100n")
      (footprint "eagle-import:C0402")
      (libsource (lib "eagle-import") (part "C-EUC0402"))
    )
    (comp (ref "C26")
      (value "100n")
      (footprint "eagle-import:C0402")
      (libsource (lib "eagle-import") (part "C-EUC0402"))
    )
    (comp (ref "C27")
      (value "10u")
      (footprint "eagle-import:C0603")
      (libsource (lib "eagle-import") (part "rcl_334_C-EUC0603"))
    )
    (comp (ref "C28")
      (value "NFM18CC101R1C3D")
      (footprint "eagle-import:NFM18PC")
      (libsource (lib "eagle-import") (part "NFM18CC101R1C3D"))
    )
    (comp (ref "C29")
      (value "NFM18CC101R1C3D")
      (footprint "eagle-import:NFM18PC")
      (libsource (lib "eagle-import") (part "NFM18CC101R1C3D"))
    )
    (comp (ref "C30")
      (value "NFM18CC101R1C3D")
      (footprint "eagle-import:NFM18PC")
      (libsource (lib "eagle-import") (part "NFM18CC101R1C3D"))
    )
    (comp (ref "C31")
      (value "NFM18CC101R1C3D")
      (footprint "eagle-import:NFM18PC")
      (libsource (lib "eagle-import") (part "NFM18CC101R1C3D"))
    )
    (comp (ref "C32")
      (value "NFM18CC101R1C3D")
      (footprint "eagle-import:NFM18PC")
      (libsource (lib "eagle-import") (part "NFM18CC101R1C3D"))
    )
    (comp (ref "C33")
      (value "NFM18CC101R1C3D")
      (footprint "eagle-import:NFM18PC")
      (libsource (lib "eagle-import") (part "NFM18CC101R1C3D"))
    )
    (comp (ref "C34")
      (value "NFM21PC475B1A3D")
      (footprint "eagle-import:NFM21PC")
      (libsource (lib "eagle-import") (part "NFM21PC475B1A3D"))
    )
    (comp (ref "C35")
      (value "10u")
      (footprint "eagle-import:C0603")
      (libsource (lib "eagle-import") (part "rcl_334_C-EUC0603"))
    )
    (comp (ref "C37")
      (value "10n")
      (footprint "eagle-import:C0402")
      (libsource (lib "eagle-import") (part "C-EUC0402"))
    )
    (comp (ref "C38")
      (value "10n")
      (footprint "eagle-import:C0402")
      (libsource (lib "eagle-import") (part "C-EUC0402"))
    )
    (comp (ref "C39")
      (value "1n")
      (footprint "eagle-import:C0402")
      (libsource (lib "eagle-import") (part "C-EUC0402"))
    )
    (comp (ref "IC1")
      (value "STW81200")
      (footprint "eagle-import:QFN50P600X600X100-37T410N")
      (libsource (lib "eagle-import") (part "STW81200"))
    )
    (comp (ref "JP1")
      (value "PINHD-1X3")
      (footprint "eagle-import:1X03")
      (libsource (lib "eagle-import") (part "PINHD-1X3"))
    )
    (comp (ref "JP4")
      (value "PINHD-1X8")
      (footprint "eagle-import:1X08")
      (libsource (lib "eagle-import") (part "PINHD-1X8"))
    )
    (comp (ref "JP5")
      (value "PINHD-2X5")
      (footprint "eagle-import:2X05")
      (libsource (lib "eagle-import") (part "PINHD-2X5"))
    )
    (comp (ref "L1")
      (value "FERRITE")
      (footprint "eagle-import:R0402")
      (libsource (lib "eagle-import") (part "FERRITE"))
    )
    (comp (ref "L2")
      (value "FERRITE")
      (footprint "eagle-import:R0402")
      (libsource (lib "eagle-import") (part "FERRITE"))
    )
    (comp (ref "R1")
      (value "0R2")
      (footprint "eagle-import:R0402")
      (libsource (lib "eagle-import") (part "R-EU_R0402"))
    )
    (comp (ref "R2")
      (value "0R5")
      (footprint "eagle-import:R0402")
      (libsource (lib "eagle-import") (part "R-EU_R0402"))
    )
    (comp (ref "R3")
      (value "0R5")
      (footprint "eagle-import:R0402")
      (libsource (lib "eagle-import") (part "R-EU_R0402"))
    )
    (comp (ref "R4")
      (value "0R5")
      (footprint "eagle-import:R0402")
      (libsource (lib "eagle-import") (part "R-EU_R0402"))
    )
    (comp (ref "R5")
      (value "0R2")
      (footprint "eagle-import:R0402")
      (libsource (lib "eagle-import") (part "R-EU_R0402"))
    )
    (comp (ref "R6")
      (value "DNP")
      (footprint "eagle-import:R0402")
      (libsource (lib "eagle-import") (part "R-EU_R0402"))
    )
    (comp (ref "R7")
      (value "DNP")
      (footprint "eagle-import:R0402")
      (libsource (lib "eagle-import") (part "R-EU_R0402"))
    )
    (comp (ref "R8")
      (value "DNP")
      (footprint "eagle-import:R0402")
      (libsource (lib "eagle-import") (part "R-EU_R0402"))
    )
    (comp (ref "R9")
      (value "22")
      (footprint "eagle-import:R0402")
      (libsource (lib "eagle-import") (part "R-EU_R0402"))
    )
    (comp (ref "R10")
      (value "22")
      (footprint "eagle-import:R0402")
      (libsource (lib "eagle-import") (part "R-EU_R0402"))
    )
    (comp (ref "R11")
      (value "22")
      (footprint "eagle-import:R0402")
      (libsource (lib "eagle-import") (part "R-EU_R0402"))
    )
    (comp (ref "R12")
      (value "22")
      (footprint "eagle-import:R0402")
      (libsource (lib "eagle-import") (part "R-EU_R0402"))
    )
    (comp (ref "R13")
      (value "22")
      (footprint "eagle-import:R0402")
      (libsource (lib "eagle-import") (part "R-EU_R0402"))
    )
    (comp (ref "R14")
      (value "22")
      (footprint "eagle-import:R0402")
      (libsource (lib "eagle-import") (part "R-EU_R0402"))
    )
    (comp (ref "R15")
      (value "22")
      (footprint "eagle-import:R0402")
      (libsource (lib "eagle-import") (part "R-EU_R0402"))
    )
    (comp (ref "R16")
      (value "22")
      (footprint "eagle-import:R0402")
      (libsource (lib "eagle-import") (part "R-EU_R0402"))
    )
    (comp (ref "R17")
      (value "22")
      (footprint "eagle-import:R0402")
      (libsource (lib "eagle-import") (part "R-EU_R0402"))
    )
    (comp (ref "R18")
      (value "22")
      (footprint "eagle-import:R0402")
      (libsource (lib "eagle-import") (part "R-EU_R0402"))
    )
    (comp (ref "R19")
      (value "22")
      (footprint "eagle-import:R0402")
      (libsource (lib "eagle-import") (part "R-EU_R0402"))
    )
    (comp (ref "R20")
      (value "22")
      (footprint "eagle-import:R0402")
      (libsource (lib "eagle-import") (part "R-EU_R0402"))
    )
    (comp (ref "R21")
      (value "0")
      (footprint "eagle-import:R0402")
      (libsource (lib "eagle-import") (part "R-EU_R0402"))
    )
    (comp (ref "R22")
      (value "0")
      (footprint "eagle-import:R0402")
      (libsource (lib "eagle-import") (part "R-EU_R0402"))
    )
    (comp (ref "R27")
      (value "DNP")
      (footprint "eagle-import:R0402")
      (libsource (lib "eagle-import") (part "R-EU_R0402"))
    )
    (comp (ref "R28")
      (value "DNP")
      (footprint "eagle-import:R0402")
      (libsource (lib "eagle-import") (part "R-EU_R0402"))
    )
    (comp (ref "SH1")
      (value "TE_2118718-2")
      (footprint "eagle-import:TE_2118718-2")
      (libsource (lib "eagle-import") (part "TE_2118718-2"))
    )
    (comp (ref "T1")
      (value "B012-617DB-1-63-B331")
      (footprint "eagle-import:EASTEVER_BALUN")
      (libsource (lib "eagle-import") (part "B012-617DB-1-63-B331"))
    )
    (comp (ref "X1")
      (value "SMA_CONNECTOR")
      (footprint "eagle-import:J502-ND-142-0711-821_826")
      (libsource (lib "eagle-import") (part "SMA_CONNECTOR"))
    )
    (comp (ref "X2")
      (value "SMA_CONNECTOR")
      (footprint "eagle-import:J502-ND-142-0711-821_826")
      (libsource (lib "eagle-import") (part "SMA_CONNECTOR"))
    )
    (comp (ref "X3")
      (value "SMA_CONNECTOR")
      (footprint "eagle-import:J502-ND-142-0711-821_826")
      (libsource (lib "eagle-import") (part "SMA_CONNECTOR"))
    )
    (comp (ref "X5")
      (value "SMA_CONNECTOR")
      (footprint "eagle-import:J502-ND-142-0711-821_826")
      (libsource (lib "eagle-import") (part "SMA_CONNECTOR"))
    )
  )
  (nets
    (net (code "1") (name "+3V3") (class "Default")
      (node (ref "C61") (pin "1") (pinfunction "1_1") (pintype "passive"))
      (node (ref "C63") (pin "1") (pinfunction "1_1") (pintype "passive"))
      (node (ref "C64") (pin "1") (pinfunction "1_1") (pintype "passive"))
      (node (ref "C65") (pin "1") (pinfunction "1_1") (pintype "passive"))
      (node (ref "C66") (pin "1") (pinfunction "1_1") (pintype "passive"))
      (node (ref "C67") (pin "1") (pinfunction "1_1") (pintype "passive"))
      (node (ref "C82") (pin "1") (pinfunction "1_1") (pintype "passive"))
      (node (ref "IC19") (pin "2") (pinfunction "VOUT_2") (pintype "power_in"))
      (node (ref "IC19") (pin "4") (pinfunction "VOUT_4") (pintype "power_in"))
      (node (ref "IC4") (pin "1") (pinfunction "VDD_DIG_1") (pintype "power_in"))
      (node (ref "IC4") (pin "4") (pinfunction "VDD_XTAL_4") (pintype "power_in"))
      (node (ref "IC5") (pin "1") (pinfunction "VBAT_1") (pintype "power_in"))
      (node (ref "IC5") (pin "24") (pinfunction "VDD_24") (pintype "power_in"))
      (node (ref "IC5") (pin "36") (pinfunction "VDDUSB_36") (pintype "bidirectional"))
      (node (ref "IC5") (pin "48") (pinfunction "VDD_48") (pintype "power_in"))
      (node (ref "IC5") (pin "9") (pinfunction "VDDA/VREF+_9") (pintype "power_in"))
      (node (ref "JP9") (pin "1") (pinfunction "1_1") (pintype "passive"))
      (node (ref "L10") (pin "2") (pinfunction "2_2") (pintype "passive"))
      (node (ref "L11") (pin "2") (pinfunction "2_2") (pintype "passive"))
      (node (ref "L9") (pin "1") (pinfunction "1_1") (pintype "passive"))
      (node (ref "R26") (pin "2") (pinfunction "2_2") (pintype "passive"))
      (node (ref "R47") (pin "2") (pinfunction "2_2") (pintype "passive"))
      (node (ref "R48") (pin "2") (pinfunction "2_2") (pintype "passive"))
      (node (ref "R51") (pin "1") (pinfunction "1_1") (pintype "passive"))
    )
    (net (code "2") (name "+5V") (class "Default")
      (node (ref "C78") (pin "1") (pinfunction "1_1") (pintype "passive"))
      (node (ref "IC19") (pin "3") (pinfunction "VIN_3") (pintype "power_in"))
      (node (ref "JP1") (pin "1") (pinfunction "1_1") (pintype "passive"))
      (node (ref "JP12") (pin "2") (pinfunction "2_2") (pintype "passive"))
      (node (ref "R52") (pin "2") (pinfunction "2_2") (pintype "passive"))
    )
    (net (code "3") (name "AD9913_CS") (class "Default")
      (node (ref "IC5") (pin "25") (pinfunction "PB12_25") (pintype "bidirectional"))
      (node (ref "JP3") (pin "4") (pinfunction "4_4") (pintype "passive"))
      (node (ref "R34") (pin "1") (pinfunction "1_1") (pintype "passive"))
    )
    (net (code "4") (name "AD9913_IOUT_P") (class "Default")
      (node (ref "C46") (pin "1") (pinfunction "1_1") (pintype "passive"))
      (node (ref "IC2") (pin "20") (pinfunction "IOUT_20") (pintype "output"))
      (node (ref "L3") (pin "1") (pinfunction "1_1") (pintype "passive"))
      (node (ref "R31") (pin "2") (pinfunction "2_2") (pintype "passive"))
    )
    (net (code "5") (name "AD9913_IO_UPDATE") (class "Default")
      (node (ref "IC5") (pin "22") (pinfunction "PB11_22") (pintype "bidirectional"))
      (node (ref "JP3") (pin "5") (pinfunction "5_5") (pintype "passive"))
      (node (ref "R39") (pin "1") (pinfunction "1_1") (pintype "passive"))
    )
    (net (code "6") (name "AD9913_MRESET") (class "Default")
      (node (ref "IC5") (pin "20") (pinfunction "PB2_20") (pintype "bidirectional"))
      (node (ref "JP3") (pin "7") (pinfunction "7_7") (pintype "passive"))
      (node (ref "R37") (pin "1") (pinfunction "1_1") (pintype "passive"))
    )
    (net (code "7") (name "AD9913_OUT_N") (class "Default")
      (node (ref "B1") (pin "3") (pinfunction "SEC_DOT_3") (pintype "bidirectional"))
      (node (ref "C49") (pin "2") (pinfunction "2_2") (pintype "passive"))
      (node (ref "JP5") (pin "1") (pinfunction "1_1") (pintype "passive"))
      (node (ref "L7") (pin "1") (pinfunction "1_1") (pintype "passive"))
    )
    (net (code "8") (name "AD9913_OUT_P") (class "Default")
      (node (ref "B1") (pin "1") (pinfunction "SEC_1") (pintype "bidirectional"))
      (node (ref "C49") (pin "1") (pinfunction "1_1") (pintype "passive"))
      (node (ref "JP5") (pin "2") (pinfunction "2_2") (pintype "passive"))
      (node (ref "L5") (pin "2") (pinfunction "2_2") (pintype "passive"))
    )
    (net (code "9") (name "AD9913_PWR_DWN") (class "Default")
      (node (ref "IC5") (pin "21") (pinfunction "PB10_21") (pintype "bidirectional"))
      (node (ref "JP3") (pin "6") (pinfunction "6_6") (pintype "passive"))
      (node (ref "R38") (pin "1") (pinfunction "1_1") (pintype "passive"))
    )
    (net (code "10") (name "AD9913_REF_LVDS_N") (class "Default")
      (node (ref "IC4") (pin "21") (pinfunction "OUT3B_21") (pintype "output"))
      (node (ref "JP6") (pin "1") (pinfunction "1_1") (pintype "passive"))
    )
    (net (code "11") (name "AD9913_REF_LVDS_P") (class "Default")
      (node (ref "IC4") (pin "22") (pinfunction "OUT3_22") (pintype "output"))
      (node (ref "JP6") (pin "2") (pinfunction "2_2") (pintype "passive"))
    )
    (net (code "12") (name "AD9913_REF_N") (class "Default")
      (node (ref "C45") (pin "2") (pinfunction "2_2") (pintype "passive"))
      (node (ref "IC2") (pin "14") (pinfunction "/REF_CLK_14") (pintype "input"))
    )
    (net (code "13") (name "AD9913_REF_P") (class "Default")
      (node (ref "C44") (pin "2") (pinfunction "2_2") (pintype "passive"))
      (node (ref "IC2") (pin "13") (pinfunction "REF_CLK_13") (pintype "input"))
    )
    (net (code "14") (name "AD9913_SCLK") (class "Default")
      (node (ref "IC5") (pin "26") (pinfunction "PB13_26") (pintype "bidirectional"))
      (node (ref "JP3") (pin "2") (pinfunction "2_2") (pintype "passive"))
      (node (ref "R35") (pin "1") (pinfunction "1_1") (pintype "passive"))
    )
    (net (code "15") (name "AD9913_SDIO") (class "Default")
      (node (ref "IC5") (pin "27") (pinfunction "PB14_27") (pintype "bidirectional"))
      (node (ref "IC5") (pin "28") (pinfunction "PB15_28") (pintype "bidirectional"))
      (node (ref "JP3") (pin "3") (pinfunction "3_3") (pintype "passive"))
      (node (ref "R36") (pin "1") (pinfunction "1_1") (pintype "passive"))
      (node (ref "R46") (pin "1") (pinfunction "1_1") (pintype "passive"))
    )
    (net (code "16") (name "GND") (class "Default")
      (node (ref "B1") (pin "4") (pinfunction "PRI_DOT_4") (pintype "bidirectional"))
      (node (ref "C1") (pin "2") (pinfunction "2_2") (pintype "passive"))
      (node (ref "C10") (pin "2") (pinfunction "2_2") (pintype "passive"))
      (node (ref "C11") (pin "2") (pinfunction "2_2") (pintype "passive"))
      (node (ref "C12") (pin "2") (pinfunction "2_2") (pintype "passive"))
      (node (ref "C13") (pin "2") (pinfunction "2_2") (pintype "passive"))
      (node (ref "C14") (pin "2") (pinfunction "2_2") (pintype "passive"))
      (node (ref "C15") (pin "2") (pinfunction "2_2") (pintype "passive"))
      (node (ref "C16") (pin "2") (pinfunction "2_2") (pintype "passive"))
      (node (ref "C17") (pin "2") (pinfunction "2_2") (pintype "passive"))
      (node (ref "C18") (pin "2") (pinfunction "2_2") (pintype "passive"))
      (node (ref "C195") (pin "2") (pinfunction "2_2") (pintype "passive"))
      (node (ref "C198") (pin "2") (pinfunction "2_2") (pintype "passive"))
      (node (ref "C2") (pin "2") (pinfunction "2_2") (pintype "passive"))
      (node (ref "C20") (pin "2") (pinfunction "2_2") (pintype "passive"))
      (node (ref "C25") (pin "2") (pinfunction "2_2") (pintype "passive"))
      (node (ref "C26") (pin "2") (pinfunction "2_2") (pintype "passive"))
      (node (ref "C27") (pin "2") (pinfunction "2_2") (pintype "passive"))
      (node (ref "C28") (pin "2") (pinfunction "2_2") (pintype "passive"))
      (node (ref "C28") (pin "4") (pinfunction "2_4") (pintype "passive"))
      (node (ref "C29") (pin "2") (pinfunction "2_2") (pintype "passive"))
      (node (ref "C29") (pin "4") (pinfunction "2_4") (pintype "passive"))
      (node (ref "C30") (pin "2") (pinfunction "2_2") (pintype "passive"))
      (node (ref "C30") (pin "4") (pinfunction "2_4") (pintype "passive"))
      (node (ref "C31") (pin "2") (pinfunction "2_2") (pintype "passive"))
      (node (ref "C31") (pin "4") (pinfunction "2_4") (pintype "passive"))
      (node (ref "C32") (pin "2") (pinfunction "2_2") (pintype "passive"))
      (node (ref "C32") (pin "4") (pinfunction "2_4") (pintype "passive"))
      (node (ref "C33") (pin "2") (pinfunction "2_2") (pintype "passive"))
      (node (ref "C33") (pin "4") (pinfunction "2_4") (pintype "passive"))
      (node (ref "C34") (pin "2") (pinfunction "2_2") (pintype "passive"))
      (node (ref "C34") (pin "4") (pinfunction "2_4") (pintype "passive"))
      (node (ref "C35") (pin "2") (pinfunction "2_2") (pintype "passive"))
      (node (ref "C40") (pin "2") (pinfunction "2_2") (pintype "passive"))
      (node (ref "C41") (pin "2") (pinfunction "2_2") (pintype "passive"))
      (node (ref "C42") (pin "2") (pinfunction "2_2") (pintype "passive"))
      (node (ref "C43") (pin "2") (pinfunction "2_2") (pintype "passive"))
      (node (ref "C5") (pin "2") (pinfunction "2_2") (pintype "passive"))
      (node (ref "C51") (pin "2") (pinfunction "2_2") (pintype "passive"))
      (node (ref "C52") (pin "2") (pinfunction "2_2") (pintype "passive"))
      (node (ref "C53") (pin "2") (pinfunction "2_2") (pintype "passive"))
      (node (ref "C54") (pin "2") (pinfunction "2_2") (pintype "passive"))
      (node (ref "C55") (pin "2") (pinfunction "2_2") (pintype "passive"))
      (node (ref "C56") (pin "2") (pinfunction "2_2") (pintype "passive"))
      (node (ref "C57") (pin "2") (pinfunction "2_2") (pintype "passive"))
      (node (ref "C59") (pin "2") (pinfunction "2_2") (pintype "passive"))
      (node (ref "C6") (pin "2") (pinfunction "2_2") (pintype "passive"))
      (node (ref "C60") (pin "2") (pinfunction "2_2") (pintype "passive"))
      (node (ref "C61") (pin "2") (pinfunction "2_2") (pintype "passive"))
      (node (ref "C62") (pin "2") (pinfunction "2_2") (pintype "passive"))
      (node (ref "C63") (pin "2") (pinfunction "2_2") (pintype "passive"))
      (node (ref "C64") (pin "2") (pinfunction "2_2") (pintype "passive"))
      (node (ref "C65") (pin "2") (pinfunction "2_2") (pintype "passive"))
      (node (ref "C66") (pin "2") (pinfunction "2_2") (pintype "passive"))
      (node (ref "C67") (pin "2") (pinfunction "2_2") (pintype "passive"))
      (node (ref "C68") (pin "2") (pinfunction "2_2") (pintype "passive"))
      (node (ref "C7") (pin "2") (pinfunction "2_2") (pintype "passive"))
      (node (ref "C78") (pin "2") (pinfunction "2_2") (pintype "passive"))
      (node (ref "C8") (pin "2") (pinfunction "2_2") (pintype "passive"))
      (node (ref "C82") (pin "2") (pinfunction "2_2") (pintype "passive"))
      (node (ref "C9") (pin "2") (pinfunction "2_2") (pintype "passive"))
      (node (ref "IC1") (pin "12") (pinfunction "EXTVCO_INP_12") (pintype "input"))
      (node (ref "IC1") (pin "13") (pinfunction "EXTVCO_INN_13") (pintype "input"))
      (node (ref "IC1") (pin "35") (pinfunction "TEST_SE_35") (pintype "input"))
      (node (ref "IC1") (pin "37") (pinfunction "GND_37") (pintype "power_in"))
      (node (ref "IC19") (pin "1") (pinfunction "GND_1") (pintype "power_in"))
      (node (ref "IC2") (pin "1") (pinfunction "PS2/ADR5/D5_1") (pintype "bidirectional"))
      (node (ref "IC2") (pin "10") (pinfunction "#SER/PAR_10") (pintype "input"))
      (node (ref "IC2") (pin "11") (pinfunction "AGND_11") (pintype "power_in"))
      (node (ref "IC2") (pin "15") (pinfunction "AGND_15") (pintype "power_in"))
      (node (ref "IC2") (pin "18") (pinfunction "AGND_18") (pintype "power_in"))
      (node (ref "IC2") (pin "2") (pinfunction "PS1/ADR4/D4_2") (pintype "bidirectional"))
      (node (ref "IC2") (pin "21") (pinfunction "AGND_21") (pintype "power_in"))
      (node (ref "IC2") (pin "23") (pinfunction "AGND_23") (pintype "power_in"))
      (node (ref "IC2") (pin "3") (pinfunction "PS0/ADR3/D3_3") (pintype "bidirectional"))
      (node (ref "IC2") (pin "31") (pinfunction "ADR7/D7_31") (pintype "bidirectional"))
      (node (ref "IC2") (pin "32") (pinfunction "ADR6/D6_32") (pintype "bidirectional"))
      (node (ref "IC2") (pin "33") (pinfunction "EP_33") (pintype "power_in"))
      (node (ref "IC2") (pin "5") (pinfunction "DGND_5") (pintype "power_in"))
      (node (ref "IC2") (pin "6") (pinfunction "ADR2/D2_6") (pintype "bidirectional"))
      (node (ref "IC2") (pin "7") (pinfunction "ADR1/D1_7") (pintype "bidirectional"))
      (node (ref "IC2") (pin "8") (pinfunction "ADR0/D0_8") (pintype "bidirectional"))
      (node (ref "IC3") (pin "2") (pinfunction "GND_2") (pintype "power_in"))
      (node (ref "IC34") (pin "2") (pinfunction "GND_2") (pintype "power_in"))
      (node (ref "IC4") (pin "33") (pinfunction "GND_33") (pintype "bidirectional"))
      (node (ref "IC5") (pin "23") (pinfunction "VSS_23") (pintype "power_in"))
      (node (ref "IC5") (pin "35") (pinfunction "VSS_35") (pintype "power_in"))
      (node (ref "IC5") (pin "44") (pinfunction "PH3-BOOT0_44") (pintype "bidirectional"))
      (node (ref "IC5") (pin "47") (pinfunction "VSS_47") (pintype "power_in"))
      (node (ref "IC5") (pin "49") (pinfunction "EP_49") (pintype "bidirectional"))
      (node (ref "IC5") (pin "8") (pinfunction "VSSA/VREF-_8") (pintype "power_in"))
      (node (ref "J1") (pin "G1") (pinfunction "2_G1") (pintype "passive"))
      (node (ref "J1") (pin "G2") (pinfunction "2_G2") (pintype "passive"))
      (node (ref "J1") (pin "G3") (pinfunction "2_G3") (pintype "passive"))
      (node (ref "J1") (pin "G4") (pinfunction "2_G4") (pintype "passive"))
      (node (ref "J2") (pin "G1") (pinfunction "2_G1") (pintype "passive"))
      (node (ref "J2") (pin "G2") (pinfunction "2_G2") (pintype "passive"))
      (node (ref "J2") (pin "G3") (pinfunction "2_G3") (pintype "passive"))
      (node (ref "J2") (pin "G4") (pinfunction "2_G4") (pintype "passive"))
      (node (ref "J3") (pin "G1") (pinfunction "2_G1") (pintype "passive"))
      (node (ref "J3") (pin "G2") (pinfunction "2_G2") (pintype "passive"))
      (node (ref "J3") (pin "G3") (pinfunction "2_G3") (pintype "passive"))
      (node (ref "J3") (pin "G4") (pinfunction "2_G4") (pintype "passive"))
      (node (ref "J4") (pin "G@1") (pinfunction "2_G@1") (pintype "passive"))
      (node (ref "J4") (pin "G@2") (pinfunction "2_G@2") (pintype "passive"))
      (node (ref "J4") (pin "G@3") (pinfunction "2_G@3") (pintype "passive"))
      (node (ref "J4") (pin "G@4") (pinfunction "2_G@4") (pintype "passive"))
      (node (ref "J5") (pin "G@1") (pinfunction "2_G@1") (pintype "passive"))
      (node (ref "J5") (pin "G@2") (pinfunction "2_G@2") (pintype "passive"))
      (node (ref "J5") (pin "G@3") (pinfunction "2_G@3") (pintype "passive"))
      (node (ref "J5") (pin "G@4") (pinfunction "2_G@4") (pintype "passive"))
      (node (ref "J6") (pin "G@1") (pinfunction "2_G@1") (pintype "passive"))
      (node (ref "J6") (pin "G@2") (pinfunction "2_G@2") (pintype "passive"))
      (node (ref "J6") (pin "G@3") (pinfunction "2_G@3") (pintype "passive"))
      (node (ref "J6") (pin "G@4") (pinfunction "2_G@4") (pintype "passive"))
      (node (ref "JP1") (pin "3") (pinfunction "3_3") (pintype "passive"))
      (node (ref "JP10") (pin "2") (pinfunction "2_2") (pintype "passive"))
      (node (ref "JP11") (pin "3") (pinfunction "3_3") (pintype "passive"))
      (node (ref "JP12") (pin "3") (pinfunction "3_3") (pintype "passive"))
      (node (ref "JP2") (pin "2") (pinfunction "2_2") (pintype "passive"))
      (node (ref "JP3") (pin "1") (pinfunction "1_1") (pintype "passive"))
      (node (ref "JP3") (pin "8") (pinfunction "8_8") (pintype "passive"))
      (node (ref "JP4") (pin "1") (pinfunction "1_1") (pintype "passive"))
      (node (ref "JP4") (pin "8") (pinfunction "8_8") (pintype "passive"))
      (node (ref "JP5") (pin "5") (pinfunction "5_5") (pintype "passive"))
      (node (ref "JP6") (pin "5") (pinfunction "5_5") (pintype "passive"))
      (node (ref "JP7") (pin "2") (pinfunction "2_2") (pintype "passive"))
      (node (ref "JP8") (pin "2") (pinfunction "2_2") (pintype "passive"))
      (node (ref "JP9") (pin "3") (pinfunction "3_3") (pintype "passive"))
      (node (ref "LED1") (pin "C") (pinfunction "C_C") (pintype "passive"))
      (node (ref "LED2") (pin "C") (pinfunction "C_C") (pintype "passive"))
      (node (ref "LED3") (pin "C") (pinfunction "C_C") (pintype "passive"))
      (node (ref "LED4") (pin "C") (pinfunction "C_C") (pintype "passive"))
      (node (ref "LED5") (pin "C") (pinfunction "C_C") (pintype "passive"))
      (node (ref "Q1") (pin "2") (pinfunction "2_2") (pintype "passive"))
      (node (ref "Q1") (pin "4") (pinfunction "4_4") (pintype "passive"))
      (node (ref "R23") (pin "1") (pinfunction "1_1") (pintype "passive"))
      (node (ref "R24") (pin "1") (pinfunction "1_1") (pintype "passive"))
      (node (ref "R25") (pin "1") (pinfunction "1_1") (pintype "passive"))
      (node (ref "R27") (pin "2") (pinfunction "2_2") (pintype "passive"))
      (node (ref "R28") (pin "2") (pinfunction "2_2") (pintype "passive"))
      (node (ref "R29") (pin "1") (pinfunction "1_1") (pintype "passive"))
      (node (ref "R30") (pin "1") (pinfunction "1_1") (pintype "passive"))
      (node (ref "R31") (pin "1") (pinfunction "1_1") (pintype "passive"))
      (node (ref "R33") (pin "1") (pinfunction "1_1") (pintype "passive"))
      (node (ref "R40") (pin "1") (pinfunction "1_1") (pintype "passive"))
      (node (ref "R41") (pin "1") (pinfunction "1_1") (pintype "passive"))
      (node (ref "R42") (pin "1") (pinfunction "1_1") (pintype "passive"))
      (node (ref "R43") (pin "1") (pinfunction "1_1") (pintype "passive"))
      (node (ref "R44") (pin "1") (pinfunction "1_1") (pintype "passive"))
      (node (ref "R45") (pin "1") (pinfunction "1_1") (pintype "passive"))
      (node (ref "R6") (pin "1") (pinfunction "1_1") (pintype "passive"))
      (node (ref "SH1") (pin "1") (pinfunction "GND_1") (pintype "bidirectional"))
      (node (ref "SH1") (pin "10") (pinfunction "GND_10") (pintype "bidirectional"))
      (node (ref "SH1") (pin "11") (pinfunction "GND_11") (pintype "bidirectional"))
      (node (ref "SH1") (pin "12") (pinfunction "GND_12") (pintype "bidirectional"))
      (node (ref "SH1") (pin "13") (pinfunction "GND_13") (pintype "bidirectional"))
      (node (ref "SH1") (pin "14") (pinfunction "GND_14") (pintype "bidirectional"))
      (node (ref "SH1") (pin "15") (pinfunction "GND_15") (pintype "bidirectional"))
      (node (ref "SH1") (pin "16") (pinfunction "GND_16") (pintype "bidirectional"))
      (node (ref "SH1") (pin "17") (pinfunction "GND_17") (pintype "bidirectional"))
      (node (ref "SH1") (pin "18") (pinfunction "GND_18") (pintype "bidirectional"))
      (node (ref "SH1") (pin "19") (pinfunction "GND_19") (pintype "bidirectional"))
      (node (ref "SH1") (pin "2") (pinfunction "GND_2") (pintype "bidirectional"))
      (node (ref "SH1") (pin "20") (pinfunction "GND_20") (pintype "bidirectional"))
      (node (ref "SH1") (pin "3") (pinfunction "GND_3") (pintype "bidirectional"))
      (node (ref "SH1") (pin "4") (pinfunction "GND_4") (pintype "bidirectional"))
      (node (ref "SH1") (pin "5") (pinfunction "GND_5") (pintype "bidirectional"))
      (node (ref "SH1") (pin "6") (pinfunction "GND_6") (pintype "bidirectional"))
      (node (ref "SH1") (pin "7") (pinfunction "GND_7") (pintype "bidirectional"))
      (node (ref "SH1") (pin "8") (pinfunction "GND_8") (pintype "bidirectional"))
      (node (ref "SH1") (pin "9") (pinfunction "GND_9") (pintype "bidirectional"))
      (node (ref "SJ1") (pin "1") (pinfunction "1_1") (pintype "passive"))
      (node (ref "T1") (pin "2") (pinfunction "IN-_2") (pintype "bidirectional"))
      (node (ref "X1") (pin "G@1") (pinfunction "2_G@1") (pintype "passive"))
      (node (ref "X1") (pin "G@2") (pinfunction "2_G@2") (pintype "passive"))
      (node (ref "X1") (pin "G@3") (pinfunction "2_G@3") (pintype "passive"))
      (node (ref "X1") (pin "G@4") (pinfunction "2_G@4") (pintype "passive"))
      (node (ref "X10") (pin "5") (pinfunction "5_5") (pintype "passive"))
      (node (ref "X10") (pin "M1") (pinfunction "S1_M1") (pintype "passive"))
      (node (ref "X10") (pin "M2") (pinfunction "S2_M2") (pintype "passive"))
      (node (ref "X10") (pin "M3") (pinfunction "S3_M3") (pintype "passive"))
      (node (ref "X10") (pin "M4") (pinfunction "S4_M4") (pintype "passive"))
      (node (ref "X2") (pin "G@1") (pinfunction "2_G@1") (pintype "passive"))
      (node (ref "X2") (pin "G@2") (pinfunction "2_G@2") (pintype "passive"))
      (node (ref "X2") (pin "G@3") (pinfunction "2_G@3") (pintype "passive"))
      (node (ref "X2") (pin "G@4") (pinfunction "2_G@4") (pintype "passive"))
      (node (ref "X3") (pin "G@1") (pinfunction "2_G@1") (pintype "passive"))
      (node (ref "X3") (pin "G@2") (pinfunction "2_G@2") (pintype "passive"))
      (node (ref "X3") (pin "G@3") (pinfunction "2_G@3") (pintype "passive"))
      (node (ref "X3") (pin "G@4") (pinfunction "2_G@4") (pintype "passive"))
      (node (ref "X4") (pin "G@1") (pinfunction "2_G@1") (pintype "passive"))
      (node (ref "X4") (pin "G@2") (pinfunction "2_G@2") (pintype "passive"))
      (node (ref "X4") (pin "G@3") (pinfunction "2_G@3") (pintype "passive"))
      (node (ref "X4") (pin "G@4") (pinfunction "2_G@4") (pintype "passive"))
      (node (ref "X5") (pin "G@1") (pinfunction "2_G@1") (pintype "passive"))
      (node (ref "X5") (pin "G@2") (pinfunction "2_G@2") (pintype "passive"))
      (node (ref "X5") (pin "G@3") (pinfunction "2_G@3") (pintype "passive"))
      (node (ref "X5") (pin "G@4") (pinfunction "2_G@4") (pintype "passive"))
      (node (ref "X6") (pin "G@1") (pinfunction "2_G@1") (pintype "passive"))
      (node (ref "X6") (pin "G@2") (pinfunction "2_G@2") (pintype "passive"))
      (node (ref "X6") (pin "G@3") (pinfunction "2_G@3") (pintype "passive"))
      (node (ref "X6") (pin "G@4") (pinfunction "2_G@4") (pintype "passive"))
      (node (ref "X7") (pin "G@1") (pinfunction "2_G@1") (pintype "passive"))
      (node (ref "X7") (pin "G@2") (pinfunction "2_G@2") (pintype "passive"))
      (node (ref "X7") (pin "G@3") (pinfunction "2_G@3") (pintype "passive"))
      (node (ref "X7") (pin "G@4") (pinfunction "2_G@4") (pintype "passive"))
      (node (ref "X8") (pin "G@1") (pinfunction "2_G@1") (pintype "passive"))
      (node (ref "X8") (pin "G@2") (pinfunction "2_G@2") (pintype "passive"))
      (node (ref "X8") (pin "G@3") (pinfunction "2_G@3") (pintype "passive"))
      (node (ref "X8") (pin "G@4") (pinfunction "2_G@4") (pintype "passive"))
      (node (ref "X9") (pin "G@1") (pinfunction "2_G@1") (pintype "passive"))
      (node (ref "X9") (pin "G@2") (pinfunction "2_G@2") (pintype "passive"))
      (node (ref "X9") (pin "G@3") (pinfunction "2_G@3") (pintype "passive"))
      (node (ref "X9") (pin "G@4") (pinfunction "2_G@4") (pintype "passive"))
    )
    (net (code "17") (name "Net-(B1-PRI)") (class "Default")
      (node (ref "B1") (pin "5") (pinfunction "PRI_5") (pintype "bidirectional"))
      (node (ref "C50") (pin "1") (pinfunction "1_1") (pintype "passive"))
    )
    (net (code "18") (name "Net-(B1-SEC_CT)") (class "Default")
      (node (ref "B1") (pin "2") (pinfunction "SEC_CT_2") (pintype "bidirectional"))
      (node (ref "SJ1") (pin "2") (pinfunction "2_2") (pintype "passive"))
    )
    (net (code "19") (name "Net-(C7-Pad1)") (class "Default")
      (node (ref "C7") (pin "1") (pinfunction "1_1") (pintype "passive"))
      (node (ref "R2") (pin "2") (pinfunction "2_2") (pintype "passive"))
    )
    (net (code "20") (name "Net-(C19-Pad2)") (class "Default")
      (node (ref "C19") (pin "2") (pinfunction "2_2") (pintype "passive"))
      (node (ref "R6") (pin "2") (pinfunction "2_2") (pintype "passive"))
      (node (ref "R7") (pin "2") (pinfunction "2_2") (pintype "passive"))
    )
    (net (code "21") (name "Net-(C21-Pad2)") (class "Default")
      (node (ref "C21") (pin "2") (pinfunction "2_2") (pintype "passive"))
      (node (ref "R21") (pin "2") (pinfunction "2_2") (pintype "passive"))
      (node (ref "R27") (pin "1") (pinfunction "1_1") (pintype "passive"))
    )
    (net (code "22") (name "Net-(C22-Pad2)") (class "Default")
      (node (ref "C22") (pin "2") (pinfunction "2_2") (pintype "passive"))
      (node (ref "R22") (pin "2") (pinfunction "2_2") (pintype "passive"))
      (node (ref "R28") (pin "1") (pinfunction "1_1") (pintype "passive"))
    )
    (net (code "23") (name "Net-(C28-Pad1)") (class "Default")
      (node (ref "C28") (pin "1") (pinfunction "1_1") (pintype "passive"))
      (node (ref "R10") (pin "1") (pinfunction "1_1") (pintype "passive"))
    )
    (net (code "24") (name "Net-(C28-Pad3)") (class "Default")
      (node (ref "C28") (pin "3") (pinfunction "3_3") (pintype "passive"))
      (node (ref "R9") (pin "2") (pinfunction "2_2") (pintype "passive"))
    )
    (net (code "25") (name "Net-(C29-Pad1)") (class "Default")
      (node (ref "C29") (pin "1") (pinfunction "1_1") (pintype "passive"))
      (node (ref "R12") (pin "1") (pinfunction "1_1") (pintype "passive"))
    )
    (net (code "26") (name "Net-(C29-Pad3)") (class "Default")
      (node (ref "C29") (pin "3") (pinfunction "3_3") (pintype "passive"))
      (node (ref "R11") (pin "2") (pinfunction "2_2") (pintype "passive"))
    )
    (net (code "27") (name "Net-(C30-Pad1)") (class "Default")
      (node (ref "C30") (pin "1") (pinfunction "1_1") (pintype "passive"))
      (node (ref "R14") (pin "1") (pinfunction "1_1") (pintype "passive"))
    )
    (net (code "28") (name "Net-(C30-Pad3)") (class "Default")
      (node (ref "C30") (pin "3") (pinfunction "3_3") (pintype "passive"))
      (node (ref "R13") (pin "2") (pinfunction "2_2") (pintype "passive"))
    )
    (net (code "29") (name "Net-(C31-Pad1)") (class "Default")
      (node (ref "C31") (pin "1") (pinfunction "1_1") (pintype "passive"))
      (node (ref "R16") (pin "1") (pinfunction "1_1") (pintype "passive"))
    )
    (net (code "30") (name "Net-(C31-Pad3)") (class "Default")
      (node (ref "C31") (pin "3") (pinfunction "3_3") (pintype "passive"))
      (node (ref "R15") (pin "2") (pinfunction "2_2") (pintype "passive"))
    )
    (net (code "31") (name "Net-(C32-Pad1)") (class "Default")
      (node (ref "C32") (pin "1") (pinfunction "1_1") (pintype "passive"))
      (node (ref "R18") (pin "1") (pinfunction "1_1") (pintype "passive"))
    )
    (net (code "32") (name "Net-(C32-Pad3)") (class "Default")
      (node (ref "C32") (pin "3") (pinfunction "3_3") (pintype "passive"))
      (node (ref "R17") (pin "2") (pinfunction "2_2") (pintype "passive"))
    )
    (net (code "33") (name "Net-(C33-Pad1)") (class "Default")
      (node (ref "C33") (pin "1") (pinfunction "1_1") (pintype "passive"))
      (node (ref "R20") (pin "1") (pinfunction "1_1") (pintype "passive"))
    )
    (net (code "34") (name "Net-(C33-Pad3)") (class "Default")
      (node (ref "C33") (pin "3") (pinfunction "3_3") (pintype "passive"))
      (node (ref "R19") (pin "2") (pinfunction "2_2") (pintype "passive"))
    )
    (net (code "35") (name "Net-(C34-Pad1)") (class "Default")
      (node (ref "C34") (pin "1") (pinfunction "1_1") (pintype "passive"))
      (node (ref "L2") (pin "2") (pinfunction "2_2") (pintype "passive"))
    )
    (net (code "36") (name "Net-(C34-Pad3)") (class "Default")
      (node (ref "C34") (pin "3") (pinfunction "3_3") (pintype "passive"))
      (node (ref "L1") (pin "1") (pinfunction "1_1") (pintype "passive"))
    )
    (net (code "37") (name "Net-(C36-Pad1)") (class "Default")
      (node (ref "C36") (pin "1") (pinfunction "1_1") (pintype "passive"))
      (node (ref "X4") (pin "1") (pinfunction "1_1") (pintype "passive"))
    )
    (net (code "38") (name "Net-(C36-Pad2)") (class "Default")
      (node (ref "C36") (pin "2") (pinfunction "2_2") (pintype "passive"))
      (node (ref "JP6") (pin "6") (pinfunction "6_6") (pintype "passive"))
      (node (ref "R33") (pin "2") (pinfunction "2_2") (pintype "passive"))
    )
    (net (code "39") (name "Net-(C37-Pad1)") (class "Default")
      (node (ref "C37") (pin "1") (pinfunction "1_1") (pintype "passive"))
      (node (ref "JP5") (pin "3") (pinfunction "3_3") (pintype "passive"))
      (node (ref "JP5") (pin "7") (pinfunction "7_7") (pintype "passive"))
    )
    (net (code "40") (name "Net-(C38-Pad2)") (class "Default")
      (node (ref "C38") (pin "2") (pinfunction "2_2") (pintype "passive"))
      (node (ref "JP5") (pin "4") (pinfunction "4_4") (pintype "passive"))
      (node (ref "JP5") (pin "8") (pinfunction "8_8") (pintype "passive"))
    )
    (net (code "41") (name "Net-(C39-Pad2)") (class "Default")
      (node (ref "C39") (pin "2") (pinfunction "2_2") (pintype "passive"))
      (node (ref "X3") (pin "1") (pinfunction "1_1") (pintype "passive"))
    )
    (net (code "42") (name "Net-(C44-Pad1)") (class "Default")
      (node (ref "C44") (pin "1") (pinfunction "1_1") (pintype "passive"))
      (node (ref "JP6") (pin "4") (pinfunction "4_4") (pintype "passive"))
      (node (ref "R32") (pin "2") (pinfunction "2_2") (pintype "passive"))
    )
    (net (code "43") (name "Net-(C45-Pad1)") (class "Default")
      (node (ref "C45") (pin "1") (pinfunction "1_1") (pintype "passive"))
      (node (ref "JP6") (pin "3") (pinfunction "3_3") (pintype "passive"))
      (node (ref "R32") (pin "1") (pinfunction "1_1") (pintype "passive"))
    )
    (net (code "44") (name "Net-(C47-Pad1)") (class "Default")
      (node (ref "C47") (pin "1") (pinfunction "1_1") (pintype "passive"))
      (node (ref "L3") (pin "2") (pinfunction "2_2") (pintype "passive"))
      (node (ref "L4") (pin "1") (pinfunction "1_1") (pintype "passive"))
    )
    (net (code "45") (name "Net-(C47-Pad2)") (class "Default")
      (node (ref "C47") (pin "2") (pinfunction "2_2") (pintype "passive"))
      (node (ref "L6") (pin "1") (pinfunction "1_1") (pintype "passive"))
      (node (ref "L8") (pin "2") (pinfunction "2_2") (pintype "passive"))
    )
    (net (code "46") (name "Net-(C48-Pad1)") (class "Default")
      (node (ref "C48") (pin "1") (pinfunction "1_1") (pintype "passive"))
      (node (ref "L4") (pin "2") (pinfunction "2_2") (pintype "passive"))
      (node (ref "L5") (pin "1") (pinfunction "1_1") (pintype "passive"))
    )
    (net (code "47") (name "Net-(C48-Pad2)") (class "Default")
      (node (ref "C48") (pin "2") (pinfunction "2_2") (pintype "passive"))
      (node (ref "L7") (pin "2") (pinfunction "2_2") (pintype "passive"))
      (node (ref "L8") (pin "1") (pinfunction "1_1") (pintype "passive"))
    )
    (net (code "48") (name "Net-(C50-Pad2)") (class "Default")
      (node (ref "C50") (pin "2") (pinfunction "2_2") (pintype "passive"))
      (node (ref "X6") (pin "1") (pinfunction "1_1") (pintype "passive"))
    )
    (net (code "49") (name "Net-(C58-Pad1)") (class "Default")
      (node (ref "C58") (pin "1") (pinfunction "1_1") (pintype "passive"))
      (node (ref "X7") (pin "1") (pinfunction "1_1") (pintype "passive"))
    )
    (net (code "50") (name "Net-(IC1A-CBYP)") (class "Default")
      (node (ref "C4") (pin "2") (pinfunction "2_2") (pintype "passive"))
      (node (ref "IC1") (pin "7") (pinfunction "CBYP_7") (pintype "passive"))
    )
    (net (code "51") (name "Net-(IC1A-CBYP_4V5)") (class "Default")
      (node (ref "C3") (pin "2") (pinfunction "2_2") (pintype "passive"))
      (node (ref "IC1") (pin "1") (pinfunction "CBYP_4V5_1") (pintype "passive"))
    )
    (net (code "52") (name "Net-(IC1A-VIN_LDO_4V5)") (class "Default")
      (node (ref "C25") (pin "1") (pinfunction "1_1") (pintype "passive"))
      (node (ref "C26") (pin "1") (pinfunction "1_1") (pintype "passive"))
      (node (ref "C27") (pin "1") (pinfunction "1_1") (pintype "passive"))
      (node (ref "C35") (pin "1") (pinfunction "1_1") (pintype "passive"))
      (node (ref "IC1") (pin "18") (pinfunction "VIN_LDO_REF_18") (pintype "power_in"))
      (node (ref "IC1") (pin "28") (pinfunction "VIN_LDO_RF_DIG_28") (pintype "power_in"))
      (node (ref "IC1") (pin "36") (pinfunction "VIN_LDO_4V5_36") (pintype "power_in"))
      (node (ref "IC1") (pin "9") (pinfunction "VIN_LDO_VCO_9") (pintype "power_in"))
      (node (ref "L1") (pin "2") (pinfunction "2_2") (pintype "passive"))
    )
    (net (code "53") (name "Net-(IC1A-VR)") (class "Default")
      (node (ref "C1") (pin "1") (pinfunction "1_1") (pintype "passive"))
      (node (ref "C2") (pin "1") (pinfunction "1_1") (pintype "passive"))
      (node (ref "IC1") (pin "10") (pinfunction "VR_10") (pintype "passive"))
    )
    (net (code "54") (name "Net-(IC1A-VREG_RF)") (class "Default")
      (node (ref "IC1") (pin "29") (pinfunction "VREG_RF_29") (pintype "output"))
      (node (ref "R2") (pin "1") (pinfunction "1_1") (pintype "passive"))
    )
    (net (code "55") (name "Net-(IC1B-HW_PD)") (class "Default")
      (node (ref "IC1") (pin "4") (pinfunction "HW_PD_4") (pintype "input"))
      (node (ref "R17") (pin "1") (pinfunction "1_1") (pintype "passive"))
    )
    (net (code "56") (name "Net-(IC1B-ICP)") (class "Default")
      (node (ref "C18") (pin "1") (pinfunction "1_1") (pintype "passive"))
      (node (ref "C19") (pin "1") (pinfunction "1_1") (pintype "passive"))
      (node (ref "IC1") (pin "15") (pinfunction "ICP_15") (pintype "output"))
      (node (ref "R8") (pin "2") (pinfunction "2_2") (pintype "passive"))
    )
    (net (code "57") (name "Net-(IC1B-LD_SDO)") (class "Default")
      (node (ref "IC1") (pin "22") (pinfunction "LD_SDO_22") (pintype "output"))
      (node (ref "R13") (pin "1") (pinfunction "1_1") (pintype "passive"))
    )
    (net (code "58") (name "Net-(IC1B-LE)") (class "Default")
      (node (ref "IC1") (pin "25") (pinfunction "LE_25") (pintype "input"))
      (node (ref "R15") (pin "1") (pinfunction "1_1") (pintype "passive"))
    )
    (net (code "59") (name "Net-(IC1B-PD_RF1)") (class "Default")
      (node (ref "IC1") (pin "5") (pinfunction "PD_RF1_5") (pintype "input"))
      (node (ref "R19") (pin "1") (pinfunction "1_1") (pintype "passive"))
    )
    (net (code "60") (name "Net-(IC1B-PD_RF2{slash}FL_SW)") (class "Default")
      (node (ref "IC1") (pin "6") (pinfunction "PD_RF2/FL_SW_6") (pintype "open_collector"))
      (node (ref "R7") (pin "1") (pinfunction "1_1") (pintype "passive"))
    )
    (net (code "61") (name "Net-(IC1B-REF_CLKN)") (class "Default")
      (node (ref "C38") (pin "1") (pinfunction "1_1") (pintype "passive"))
      (node (ref "IC1") (pin "20") (pinfunction "REF_CLKN_20") (pintype "input"))
    )
    (net (code "62") (name "Net-(IC1B-REF_CLKP)") (class "Default")
      (node (ref "C37") (pin "2") (pinfunction "2_2") (pintype "passive"))
      (node (ref "IC1") (pin "21") (pinfunction "REF_CLKP_21") (pintype "input"))
    )
    (net (code "63") (name "Net-(IC1B-RF1_OUTN)") (class "Default")
      (node (ref "C22") (pin "1") (pinfunction "1_1") (pintype "passive"))
      (node (ref "IC1") (pin "30") (pinfunction "RF1_OUTN_30") (pintype "bidirectional"))
    )
    (net (code "64") (name "Net-(IC1B-RF1_OUTP)") (class "Default")
      (node (ref "C21") (pin "1") (pinfunction "1_1") (pintype "passive"))
      (node (ref "IC1") (pin "31") (pinfunction "RF1_OUTP_31") (pintype "bidirectional"))
    )
    (net (code "65") (name "Net-(IC1B-RF2_OUTN)") (class "Default")
      (node (ref "C24") (pin "1") (pinfunction "1_1") (pintype "passive"))
      (node (ref "IC1") (pin "33") (pinfunction "RF2_OUTN_33") (pintype "bidirectional"))
    )
    (net (code "66") (name "Net-(IC1B-RF2_OUTP)") (class "Default")
      (node (ref "C23") (pin "1") (pinfunction "1_1") (pintype "passive"))
      (node (ref "IC1") (pin "34") (pinfunction "RF2_OUTP_34") (pintype "bidirectional"))
    )
    (net (code "67") (name "Net-(IC1B-SCK)") (class "Default")
      (node (ref "IC1") (pin "24") (pinfunction "SCK_24") (pintype "input"))
      (node (ref "R9") (pin "1") (pinfunction "1_1") (pintype "passive"))
    )
    (net (code "68") (name "Net-(IC1B-SDI)") (class "Default")
      (node (ref "IC1") (pin "23") (pinfunction "SDI_23") (pintype "input"))
      (node (ref "R11") (pin "1") (pinfunction "1_1") (pintype "passive"))
    )
    (net (code "69") (name "Net-(IC2-DVDD)") (class "Default")
      (node (ref "C17") (pin "1") (pinfunction "1_1") (pintype "passive"))
      (node (ref "C40") (pin "1") (pinfunction "1_1") (pintype "passive"))
      (node (ref "IC2") (pin "4") (pinfunction "DVDD_4") (pintype "power_in"))
      (node (ref "IC3") (pin "5") (pinfunction "VOUT_5") (pintype "power_in"))
    )
    (net (code "70") (name "Net-(IC2-IO_UPDATE)") (class "Default")
      (node (ref "IC2") (pin "27") (pinfunction "IO_UPDATE_27") (pintype "input"))
      (node (ref "R39") (pin "2") (pinfunction "2_2") (pintype "passive"))
      (node (ref "R45") (pin "2") (pinfunction "2_2") (pintype "passive"))
    )
    (net (code "71") (name "Net-(IC2-MASTER_RESET)") (class "Default")
      (node (ref "IC2") (pin "25") (pinfunction "MASTER_RESET_25") (pintype "input"))
      (node (ref "R37") (pin "2") (pinfunction "2_2") (pintype "passive"))
      (node (ref "R43") (pin "2") (pinfunction "2_2") (pintype "passive"))
    )
    (net (code "72") (name "Net-(IC2-PWR_DWN_CTL)") (class "Default")
      (node (ref "IC2") (pin "26") (pinfunction "PWR_DWN_CTL_26") (pintype "input"))
      (node (ref "R38") (pin "2") (pinfunction "2_2") (pintype "passive"))
      (node (ref "R44") (pin "2") (pinfunction "2_2") (pintype "passive"))
    )
    (net (code "73") (name "Net-(IC2-RSET)") (class "Default")
      (node (ref "IC2") (pin "24") (pinfunction "RSET_24") (pintype "input"))
      (node (ref "R29") (pin "2") (pinfunction "2_2") (pintype "passive"))
    )
    (net (code "74") (name "Net-(IC2-SCLK)") (class "Default")
      (node (ref "IC2") (pin "30") (pinfunction "SCLK_30") (pintype "input"))
      (node (ref "R35") (pin "2") (pinfunction "2_2") (pintype "passive"))
      (node (ref "R41") (pin "2") (pinfunction "2_2") (pintype "passive"))
    )
    (net (code "75") (name "Net-(IC2-SDIO)") (class "Default")
      (node (ref "IC2") (pin "29") (pinfunction "SDIO_29") (pintype "bidirectional"))
      (node (ref "R36") (pin "2") (pinfunction "2_2") (pintype "passive"))
      (node (ref "R42") (pin "2") (pinfunction "2_2") (pintype "passive"))
    )
    (net (code "76") (name "Net-(IC2-{slash}CS)") (class "Default")
      (node (ref "IC2") (pin "28") (pinfunction "/CS_28") (pintype "input"))
      (node (ref "R34") (pin "2") (pinfunction "2_2") (pintype "passive"))
      (node (ref "R40") (pin "2") (pinfunction "2_2") (pintype "passive"))
    )
    (net (code "77") (name "Net-(IC2-{slash}IOUT)") (class "Default")
      (node (ref "C46") (pin "2") (pinfunction "2_2") (pintype "passive"))
      (node (ref "IC2") (pin "19") (pinfunction "/IOUT_19") (pintype "output"))
      (node (ref "L6") (pin "2") (pinfunction "2_2") (pintype "passive"))
      (node (ref "R30") (pin "2") (pinfunction "2_2") (pintype "passive"))
    )
    (net (code "78") (name "Net-(IC3-EN)") (class "Default")
      (node (ref "C13") (pin "1") (pinfunction "1_1") (pintype "passive"))
      (node (ref "C195") (pin "1") (pinfunction "1_1") (pintype "passive"))
      (node (ref "IC3") (pin "1") (pinfunction "VIN_1") (pintype "power_in"))
      (node (ref "IC3") (pin "3") (pinfunction "EN_3") (pintype "input"))
      (node (ref "IC34") (pin "1") (pinfunction "VIN_1") (pintype "power_in"))
      (node (ref "IC34") (pin "3") (pinfunction "EN_3") (pintype "input"))
      (node (ref "L11") (pin "1") (pinfunction "1_1") (pintype "passive"))
      (node (ref "R46") (pin "2") (pinfunction "2_2") (pintype "passive"))
    )
    (net (code "79") (name "Net-(IC4-CLKIN_2)") (class "Default")
      (node (ref "C58") (pin "2") (pinfunction "2_2") (pintype "passive"))
      (node (ref "IC4") (pin "2") (pinfunction "CLKIN_2_2") (pintype "input"))
      (node (ref "R25") (pin "2") (pinfunction "2_2") (pintype "passive"))
    )
    (net (code "80") (name "Net-(IC4-CLKIN_2B)") (class "Default")
      (node (ref "C57") (pin "1") (pinfunction "1_1") (pintype "passive"))
      (node (ref "IC4") (pin "3") (pinfunction "CLKIN_2B_3") (pintype "input"))
    )
    (net (code "81") (name "Net-(IC4-VDDA)") (class "Default")
      (node (ref "C62") (pin "1") (pinfunction "1_1") (pintype "passive"))
      (node (ref "IC4") (pin "7") (pinfunction "VDDA_7") (pintype "power_in"))
      (node (ref "L9") (pin "2") (pinfunction "2_2") (pintype "passive"))
    )
    (net (code "82") (name "Net-(IC4-XA{slash}CLKIN1)") (class "Default")
      (node (ref "C59") (pin "1") (pinfunction "1_1") (pintype "passive"))
      (node (ref "IC4") (pin "5") (pinfunction "XA/CLKIN1_5") (pintype "input"))
      (node (ref "Q1") (pin "1") (pinfunction "1_1") (pintype "passive"))
    )
    (net (code "83") (name "Net-(IC4-XB)") (class "Default")
      (node (ref "C60") (pin "1") (pinfunction "1_1") (pintype "passive"))
      (node (ref "IC4") (pin "6") (pinfunction "XB_6") (pintype "input"))
      (node (ref "Q1") (pin "3") (pinfunction "3_3") (pintype "passive"))
    )
    (net (code "84") (name "Net-(IC5-NRST)") (class "Default")
      (node (ref "C68") (pin "1") (pinfunction "1_1") (pintype "passive"))
      (node (ref "IC5") (pin "7") (pinfunction "NRST_7") (pintype "input"))
      (node (ref "JP9") (pin "5") (pinfunction "5_5") (pintype "passive"))
      (node (ref "R26") (pin "1") (pinfunction "1_1") (pintype "passive"))
    )
    (net (code "85") (name "Net-(IC5-PA0)") (class "Default")
      (node (ref "IC5") (pin "10") (pinfunction "PA0_10") (pintype "bidirectional"))
      (node (ref "R56") (pin "2") (pinfunction "2_2") (pintype "passive"))
    )
    (net (code "86") (name "Net-(IC5-PA1)") (class "Default")
      (node (ref "IC5") (pin "11") (pinfunction "PA1_11") (pintype "bidirectional"))
      (node (ref "R55") (pin "2") (pinfunction "2_2") (pintype "passive"))
    )
    (net (code "87") (name "Net-(IC5-PA2)") (class "Default")
      (node (ref "IC5") (pin "12") (pinfunction "PA2_12") (pintype "bidirectional"))
      (node (ref "R54") (pin "2") (pinfunction "2_2") (pintype "passive"))
    )
    (net (code "88") (name "Net-(IC5-PA3)") (class "Default")
      (node (ref "IC5") (pin "13") (pinfunction "PA3_13") (pintype "bidirectional"))
      (node (ref "R53") (pin "2") (pinfunction "2_2") (pintype "passive"))
    )
    (net (code "89") (name "Net-(IC5-PA11)") (class "Default")
      (node (ref "IC5") (pin "32") (pinfunction "PA11_32") (pintype "bidirectional"))
      (node (ref "R49") (pin "1") (pinfunction "1_1") (pintype "passive"))
    )
    (net (code "90") (name "Net-(IC5-PA12)") (class "Default")
      (node (ref "IC5") (pin "33") (pinfunction "PA12_33") (pintype "bidirectional"))
      (node (ref "R50") (pin "2") (pinfunction "2_2") (pintype "passive"))
    )
    (net (code "91") (name "Net-(IC5-PA13{slash}SWDIO)") (class "Default")
      (node (ref "IC5") (pin "34") (pinfunction "PA13/SWDIO_34") (pintype "bidirectional"))
      (node (ref "JP9") (pin "4") (pinfunction "4_4") (pintype "passive"))
    )
    (net (code "92") (name "Net-(IC5-PA14{slash}SWCLK)") (class "Default")
      (node (ref "IC5") (pin "37") (pinfunction "PA14/SWCLK_37") (pintype "bidirectional"))
      (node (ref "JP9") (pin "2") (pinfunction "2_2") (pintype "passive"))
    )
    (net (code "93") (name "Net-(IC34-VOUT)") (class "Default")
      (node (ref "C198") (pin "1") (pinfunction "1_1") (pintype "passive"))
      (node (ref "C41") (pin "1") (pinfunction "1_1") (pintype "passive"))
      (node (ref "C42") (pin "1") (pinfunction "1_1") (pintype "passive"))
      (node (ref "C43") (pin "1") (pinfunction "1_1") (pintype "passive"))
      (node (ref "IC2") (pin "12") (pinfunction "AVDD_12") (pintype "power_in"))
      (node (ref "IC2") (pin "16") (pinfunction "AVDD_16") (pintype "power_in"))
      (node (ref "IC2") (pin "17") (pinfunction "AVDD_17") (pintype "power_in"))
      (node (ref "IC2") (pin "22") (pinfunction "AVDD_22") (pintype "power_in"))
      (node (ref "IC34") (pin "5") (pinfunction "VOUT_5") (pintype "power_in"))
    )
    (net (code "94") (name "Net-(J1-1)") (class "Default")
      (node (ref "J1") (pin "S") (pinfunction "1_S") (pintype "passive"))
      (node (ref "R23") (pin "2") (pinfunction "2_2") (pintype "passive"))
    )
    (net (code "95") (name "Net-(J2-1)") (class "Default")
      (node (ref "J2") (pin "S") (pinfunction "1_S") (pintype "passive"))
      (node (ref "J3") (pin "S") (pinfunction "1_S") (pintype "passive"))
    )
    (net (code "96") (name "Net-(J4-Pad1)") (class "Default")
      (node (ref "J4") (pin "1") (pinfunction "1_1") (pintype "passive"))
      (node (ref "R24") (pin "2") (pinfunction "2_2") (pintype "passive"))
    )
    (net (code "97") (name "Net-(J5-Pad1)") (class "Default")
      (node (ref "J5") (pin "1") (pinfunction "1_1") (pintype "passive"))
      (node (ref "J6") (pin "1") (pinfunction "1_1") (pintype "passive"))
    )
    (net (code "98") (name "Net-(JP1-Pad2)") (class "Default")
      (node (ref "JP1") (pin "2") (pinfunction "2_2") (pintype "passive"))
      (node (ref "L2") (pin "1") (pinfunction "1_1") (pintype "passive"))
    )
    (net (code "99") (name "Net-(JP5-Pad6)") (class "Default")
      (node (ref "JP5") (pin "6") (pinfunction "6_6") (pintype "passive"))
      (node (ref "X5") (pin "1") (pinfunction "1_1") (pintype "passive"))
    )
    (net (code "100") (name "Net-(JP12-Pad1)") (class "Default")
      (node (ref "JP12") (pin "1") (pinfunction "1_1") (pintype "passive"))
      (node (ref "X10") (pin "1") (pinfunction "1_1") (pintype "passive"))
    )
    (net (code "101") (name "Net-(LED1-PadA)") (class "Default")
      (node (ref "LED1") (pin "A") (pinfunction "A_A") (pintype "passive"))
      (node (ref "R53") (pin "1") (pinfunction "1_1") (pintype "passive"))
    )
    (net (code "102") (name "Net-(LED2-PadA)") (class "Default")
      (node (ref "LED2") (pin "A") (pinfunction "A_A") (pintype "passive"))
      (node (ref "R54") (pin "1") (pinfunction "1_1") (pintype "passive"))
    )
    (net (code "103") (name "Net-(LED3-PadA)") (class "Default")
      (node (ref "LED3") (pin "A") (pinfunction "A_A") (pintype "passive"))
      (node (ref "R52") (pin "1") (pinfunction "1_1") (pintype "passive"))
    )
    (net (code "104") (name "Net-(LED4-PadA)") (class "Default")
      (node (ref "LED4") (pin "A") (pinfunction "A_A") (pintype "passive"))
      (node (ref "R55") (pin "1") (pinfunction "1_1") (pintype "passive"))
    )
    (net (code "105") (name "Net-(LED5-PadA)") (class "Default")
      (node (ref "LED5") (pin "A") (pinfunction "A_A") (pintype "passive"))
      (node (ref "R56") (pin "1") (pinfunction "1_1") (pintype "passive"))
    )
    (net (code "106") (name "Net-(R21-Pad1)") (class "Default")
      (node (ref "R21") (pin "1") (pinfunction "1_1") (pintype "passive"))
      (node (ref "X1") (pin "1") (pinfunction "1_1") (pintype "passive"))
    )
    (net (code "107") (name "Net-(R22-Pad1)") (class "Default")
      (node (ref "R22") (pin "1") (pinfunction "1_1") (pintype "passive"))
      (node (ref "X2") (pin "1") (pinfunction "1_1") (pintype "passive"))
    )
    (net (code "108") (name "Net-(R49-Pad2)") (class "Default")
      (node (ref "R49") (pin "2") (pinfunction "2_2") (pintype "passive"))
      (node (ref "X10") (pin "2") (pinfunction "2_2") (pintype "passive"))
    )
    (net (code "109") (name "Net-(R50-Pad1)") (class "Default")
      (node (ref "R50") (pin "1") (pinfunction "1_1") (pintype "passive"))
      (node (ref "R51") (pin "2") (pinfunction "2_2") (pintype "passive"))
      (node (ref "X10") (pin "3") (pinfunction "3_3") (pintype "passive"))
    )
    (net (code "110") (name "Net-(T1-IN+)") (class "Default")
      (node (ref "C39") (pin "1") (pinfunction "1_1") (pintype "passive"))
      (node (ref "T1") (pin "3") (pinfunction "IN+_3") (pintype "bidirectional"))
    )
    (net (code "111") (name "Net-(T1-OUT+)") (class "Default")
      (node (ref "C24") (pin "2") (pinfunction "2_2") (pintype "passive"))
      (node (ref "T1") (pin "4") (pinfunction "OUT+_4") (pintype "bidirectional"))
    )
    (net (code "112") (name "Net-(T1-OUT-)") (class "Default")
      (node (ref "C23") (pin "2") (pinfunction "2_2") (pintype "passive"))
      (node (ref "T1") (pin "6") (pinfunction "OUT-_6") (pintype "bidirectional"))
    )
    (net (code "113") (name "OUT0_N") (class "Default")
      (node (ref "IC4") (pin "11") (pinfunction "OUT0B_11") (pintype "output"))
      (node (ref "JP2") (pin "3") (pinfunction "3_3") (pintype "passive"))
    )
    (net (code "114") (name "OUT0_P") (class "Default")
      (node (ref "IC4") (pin "12") (pinfunction "OUT0_12") (pintype "output"))
      (node (ref "JP2") (pin "1") (pinfunction "1_1") (pintype "passive"))
    )
    (net (code "115") (name "OUT1_N") (class "Default")
      (node (ref "IC4") (pin "14") (pinfunction "OUT1B_14") (pintype "output"))
      (node (ref "JP8") (pin "3") (pinfunction "3_3") (pintype "passive"))
    )
    (net (code "116") (name "OUT1_P") (class "Default")
      (node (ref "IC4") (pin "15") (pinfunction "OUT1_15") (pintype "output"))
      (node (ref "JP8") (pin "1") (pinfunction "1_1") (pintype "passive"))
    )
    (net (code "117") (name "OUT4_N") (class "Default")
      (node (ref "IC4") (pin "26") (pinfunction "OUT4B_26") (pintype "output"))
      (node (ref "JP7") (pin "3") (pinfunction "3_3") (pintype "passive"))
    )
    (net (code "118") (name "OUT4_P") (class "Default")
      (node (ref "IC4") (pin "27") (pinfunction "OUT4_27") (pintype "output"))
      (node (ref "JP7") (pin "1") (pinfunction "1_1") (pintype "passive"))
    )
    (net (code "119") (name "OUT5_N") (class "Default")
      (node (ref "IC4") (pin "30") (pinfunction "OUT5B_30") (pintype "output"))
      (node (ref "X9") (pin "1") (pinfunction "1_1") (pintype "passive"))
    )
    (net (code "120") (name "OUT5_P") (class "Default")
      (node (ref "IC4") (pin "31") (pinfunction "OUT5_31") (pintype "output"))
      (node (ref "X8") (pin "1") (pinfunction "1_1") (pintype "passive"))
    )
    (net (code "121") (name "RX") (class "Default")
      (node (ref "IC5") (pin "43") (pinfunction "PB7_43") (pintype "bidirectional"))
      (node (ref "JP10") (pin "3") (pinfunction "3_3") (pintype "passive"))
    )
    (net (code "122") (name "SCL") (class "Default")
      (node (ref "IC4") (pin "9") (pinfunction "SCLK_9") (pintype "input"))
      (node (ref "IC5") (pin "30") (pinfunction "PA9_30") (pintype "bidirectional"))
      (node (ref "JP11") (pin "2") (pinfunction "2_2") (pintype "passive"))
      (node (ref "R47") (pin "1") (pinfunction "1_1") (pintype "passive"))
    )
    (net (code "123") (name "SDA") (class "Default")
      (node (ref "IC4") (pin "10") (pinfunction "SDA_10") (pintype "bidirectional"))
      (node (ref "IC5") (pin "31") (pinfunction "PA10_31") (pintype "bidirectional"))
      (node (ref "JP11") (pin "1") (pinfunction "1_1") (pintype "passive"))
      (node (ref "R48") (pin "1") (pinfunction "1_1") (pintype "passive"))
    )
    (net (code "124") (name "SI5332_IN1") (class "Default")
      (node (ref "IC4") (pin "8") (pinfunction "INPUT1_8") (pintype "input"))
      (node (ref "IC5") (pin "38") (pinfunction "PA15_38") (pintype "bidirectional"))
    )
    (net (code "125") (name "SI5332_IN2") (class "Default")
      (node (ref "IC4") (pin "17") (pinfunction "INPUT2_17") (pintype "input"))
      (node (ref "IC5") (pin "29") (pinfunction "PA8_29") (pintype "bidirectional"))
    )
    (net (code "126") (name "SI5332_IN3") (class "Default")
      (node (ref "IC4") (pin "24") (pinfunction "INPUT3_24") (pintype "input"))
      (node (ref "IC5") (pin "39") (pinfunction "PB3_39") (pintype "bidirectional"))
    )
    (net (code "127") (name "SI5332_IN4") (class "Default")
      (node (ref "IC4") (pin "28") (pinfunction "INPUT4_28") (pintype "input"))
      (node (ref "IC5") (pin "40") (pinfunction "PB4_40") (pintype "bidirectional"))
    )
    (net (code "128") (name "SI5332_IN5") (class "Default")
      (node (ref "IC4") (pin "29") (pinfunction "INPUT5_29") (pintype "input"))
      (node (ref "IC5") (pin "41") (pinfunction "PB5_41") (pintype "bidirectional"))
    )
    (net (code "129") (name "SI5332_VDDO") (class "Default")
      (node (ref "C51") (pin "1") (pinfunction "1_1") (pintype "passive"))
      (node (ref "C52") (pin "1") (pinfunction "1_1") (pintype "passive"))
      (node (ref "C53") (pin "1") (pinfunction "1_1") (pintype "passive"))
      (node (ref "C54") (pin "1") (pinfunction "1_1") (pintype "passive"))
      (node (ref "C55") (pin "1") (pinfunction "1_1") (pintype "passive"))
      (node (ref "C56") (pin "1") (pinfunction "1_1") (pintype "passive"))
      (node (ref "IC4") (pin "13") (pinfunction "VDDO0_13") (pintype "power_in"))
      (node (ref "IC4") (pin "16") (pinfunction "VDDO1_16") (pintype "power_in"))
      (node (ref "IC4") (pin "20") (pinfunction "VDDO2_20") (pintype "power_in"))
      (node (ref "IC4") (pin "23") (pinfunction "VDDO3_23") (pintype "power_in"))
      (node (ref "IC4") (pin "25") (pinfunction "VDDO4_25") (pintype "power_in"))
      (node (ref "IC4") (pin "32") (pinfunction "VDDO5_32") (pintype "power_in"))
      (node (ref "L10") (pin "1") (pinfunction "1_1") (pintype "passive"))
    )
    (net (code "130") (name "STW_HW_PD") (class "Default")
      (node (ref "IC5") (pin "18") (pinfunction "PB0_18") (pintype "bidirectional"))
      (node (ref "JP4") (pin "3") (pinfunction "3_3") (pintype "passive"))
      (node (ref "R18") (pin "2") (pinfunction "2_2") (pintype "passive"))
    )
    (net (code "131") (name "STW_LD_SDO") (class "Default")
      (node (ref "IC5") (pin "16") (pinfunction "PA6_16") (pintype "bidirectional"))
      (node (ref "JP4") (pin "4") (pinfunction "4_4") (pintype "passive"))
      (node (ref "R14") (pin "2") (pinfunction "2_2") (pintype "passive"))
    )
    (net (code "132") (name "STW_LE") (class "Default")
      (node (ref "IC5") (pin "14") (pinfunction "PA4_14") (pintype "bidirectional"))
      (node (ref "JP4") (pin "7") (pinfunction "7_7") (pintype "passive"))
      (node (ref "R16") (pin "2") (pinfunction "2_2") (pintype "passive"))
    )
    (net (code "133") (name "STW_PD_RF1") (class "Default")
      (node (ref "IC5") (pin "19") (pinfunction "PB1_19") (pintype "bidirectional"))
      (node (ref "JP4") (pin "2") (pinfunction "2_2") (pintype "passive"))
      (node (ref "R20") (pin "2") (pinfunction "2_2") (pintype "passive"))
    )
    (net (code "134") (name "STW_REF_N") (class "Default")
      (node (ref "IC4") (pin "18") (pinfunction "OUT2B_18") (pintype "output"))
      (node (ref "JP5") (pin "9") (pinfunction "9_9") (pintype "passive"))
    )
    (net (code "135") (name "STW_REF_P") (class "Default")
      (node (ref "IC4") (pin "19") (pinfunction "OUT2_19") (pintype "output"))
      (node (ref "JP5") (pin "10") (pinfunction "10_10") (pintype "passive"))
    )
    (net (code "136") (name "STW_SCK") (class "Default")
      (node (ref "IC5") (pin "15") (pinfunction "PA5_15") (pintype "bidirectional"))
      (node (ref "JP4") (pin "6") (pinfunction "6_6") (pintype "passive"))
      (node (ref "R10") (pin "2") (pinfunction "2_2") (pintype "passive"))
    )
    (net (code "137") (name "STW_SDI") (class "Default")
      (node (ref "IC5") (pin "17") (pinfunction "PA7_17") (pintype "bidirectional"))
      (node (ref "JP4") (pin "5") (pinfunction "5_5") (pintype "passive"))
      (node (ref "R12") (pin "2") (pinfunction "2_2") (pintype "passive"))
    )
    (net (code "138") (name "TX") (class "Default")
      (node (ref "IC5") (pin "42") (pinfunction "PB6_42") (pintype "bidirectional"))
      (node (ref "JP10") (pin "1") (pinfunction "1_1") (pintype "passive"))
    )
    (net (code "139") (name "VREG_4V5") (class "Default")
      (node (ref "C14") (pin "1") (pinfunction "1_1") (pintype "passive"))
      (node (ref "C5") (pin "1") (pinfunction "1_1") (pintype "passive"))
      (node (ref "C6") (pin "1") (pinfunction "1_1") (pintype "passive"))
      (node (ref "IC1") (pin "16") (pinfunction "VCC_CPOUT_16") (pintype "power_in"))
      (node (ref "IC1") (pin "32") (pinfunction "VCC_RFOUT_32") (pintype "power_in"))
      (node (ref "R1") (pin "2") (pinfunction "2_2") (pintype "passive"))
    )
    (net (code "140") (name "VREG_4V5_DIRECT") (class "Default")
      (node (ref "C15") (pin "1") (pinfunction "1_1") (pintype "passive"))
      (node (ref "C3") (pin "1") (pinfunction "1_1") (pintype "passive"))
      (node (ref "IC1") (pin "2") (pinfunction "VREG_4V5_2") (pintype "output"))
      (node (ref "IC1") (pin "3") (pinfunction "VCC_VCO_CORE_3") (pintype "power_in"))
      (node (ref "R1") (pin "1") (pinfunction "1_1") (pintype "passive"))
    )
    (net (code "141") (name "VREG_DIG") (class "Default")
      (node (ref "C9") (pin "1") (pinfunction "1_1") (pintype "passive"))
      (node (ref "R3") (pin "2") (pinfunction "2_2") (pintype "passive"))
    )
    (net (code "142") (name "VREG_DIG_DIRECT") (class "Default")
      (node (ref "C8") (pin "1") (pinfunction "1_1") (pintype "passive"))
      (node (ref "IC1") (pin "26") (pinfunction "VDD_DSM_NDIV_26") (pintype "power_in"))
      (node (ref "IC1") (pin "27") (pinfunction "VREG_DIG_27") (pintype "output"))
      (node (ref "R3") (pin "1") (pinfunction "1_1") (pintype "passive"))
    )
    (net (code "143") (name "VREG_REF") (class "Default")
      (node (ref "C11") (pin "1") (pinfunction "1_1") (pintype "passive"))
      (node (ref "R4") (pin "2") (pinfunction "2_2") (pintype "passive"))
    )
    (net (code "144") (name "VREG_REF_DIRECT") (class "Default")
      (node (ref "C10") (pin "1") (pinfunction "1_1") (pintype "passive"))
      (node (ref "IC1") (pin "17") (pinfunction "VDD_PFD_17") (pintype "power_in"))
      (node (ref "IC1") (pin "19") (pinfunction "VREG_REF_19") (pintype "output"))
      (node (ref "R4") (pin "1") (pinfunction "1_1") (pintype "passive"))
    )
    (net (code "145") (name "VREG_VCO") (class "Default")
      (node (ref "C12") (pin "1") (pinfunction "1_1") (pintype "passive"))
      (node (ref "R5") (pin "2") (pinfunction "2_2") (pintype "passive"))
    )
    (net (code "146") (name "VREG_VCO_DIRECT") (class "Default")
      (node (ref "C16") (pin "1") (pinfunction "1_1") (pintype "passive"))
      (node (ref "C4") (pin "1") (pinfunction "1_1") (pintype "passive"))
      (node (ref "IC1") (pin "14") (pinfunction "VDD_CP_14") (pintype "power_in"))
      (node (ref "IC1") (pin "8") (pinfunction "VREG_VCO_8") (pintype "output"))
      (node (ref "R5") (pin "1") (pinfunction "1_1") (pintype "passive"))
    )
    (net (code "147") (name "VTUNE") (class "Default")
      (node (ref "C20") (pin "1") (pinfunction "1_1") (pintype "passive"))
      (node (ref "IC1") (pin "11") (pinfunction "VCTRL_11") (pintype "input"))
      (node (ref "R8") (pin "1") (pinfunction "1_1") (pintype "passive"))
    )
    (net (code "148") (name "unconnected-(IC2-SYNC_CLK-Pad9)") (class "Default")
      (node (ref "IC2") (pin "9") (pinfunction "SYNC_CLK_9") (pintype "output"))
    )
    (net (code "149") (name "unconnected-(IC5-PB8-Pad45)") (class "Default")
      (node (ref "IC5") (pin "45") (pinfunction "PB8_45") (pintype "bidirectional"))
    )
    (net (code "150") (name "unconnected-(IC5-PB9-Pad46)") (class "Default")
      (node (ref "IC5") (pin "46") (pinfunction "PB9_46") (pintype "bidirectional"))
    )
    (net (code "151") (name "unconnected-(IC5-PC13-Pad2)") (class "Default")
      (node (ref "IC5") (pin "2") (pinfunction "PC13_2") (pintype "bidirectional"))
    )
    (net (code "152") (name "unconnected-(IC5-PC14-OSC32_IN-Pad3)") (class "Default")
      (node (ref "IC5") (pin "3") (pinfunction "PC14-OSC32_IN_3") (pintype "bidirectional"))
    )
    (net (code "153") (name "unconnected-(IC5-PC15-OSC32_OUT-Pad4)") (class "Default")
      (node (ref "IC5") (pin "4") (pinfunction "PC15-OSC32_OUT_4") (pintype "bidirectional"))
    )
    (net (code "154") (name "unconnected-(IC5-PH0-OSC_IN-Pad5)") (class "Default")
      (node (ref "IC5") (pin "5") (pinfunction "PH0-OSC_IN_5") (pintype "bidirectional"))
    )
    (net (code "155") (name "unconnected-(IC5-PH1_OSC_OUT-Pad6)") (class "Default")
      (node (ref "IC5") (pin "6") (pinfunction "PH1_OSC_OUT_6") (pintype "bidirectional"))
    )
    (net (code "156") (name "unconnected-(X10-Pad4)") (class "Default")
      (node (ref "X10") (pin "4") (pinfunction "4_4") (pintype "passive"))
    )
  )
)
